# draft6.net
KiCad netlist of a schematic drawn in EAGLE
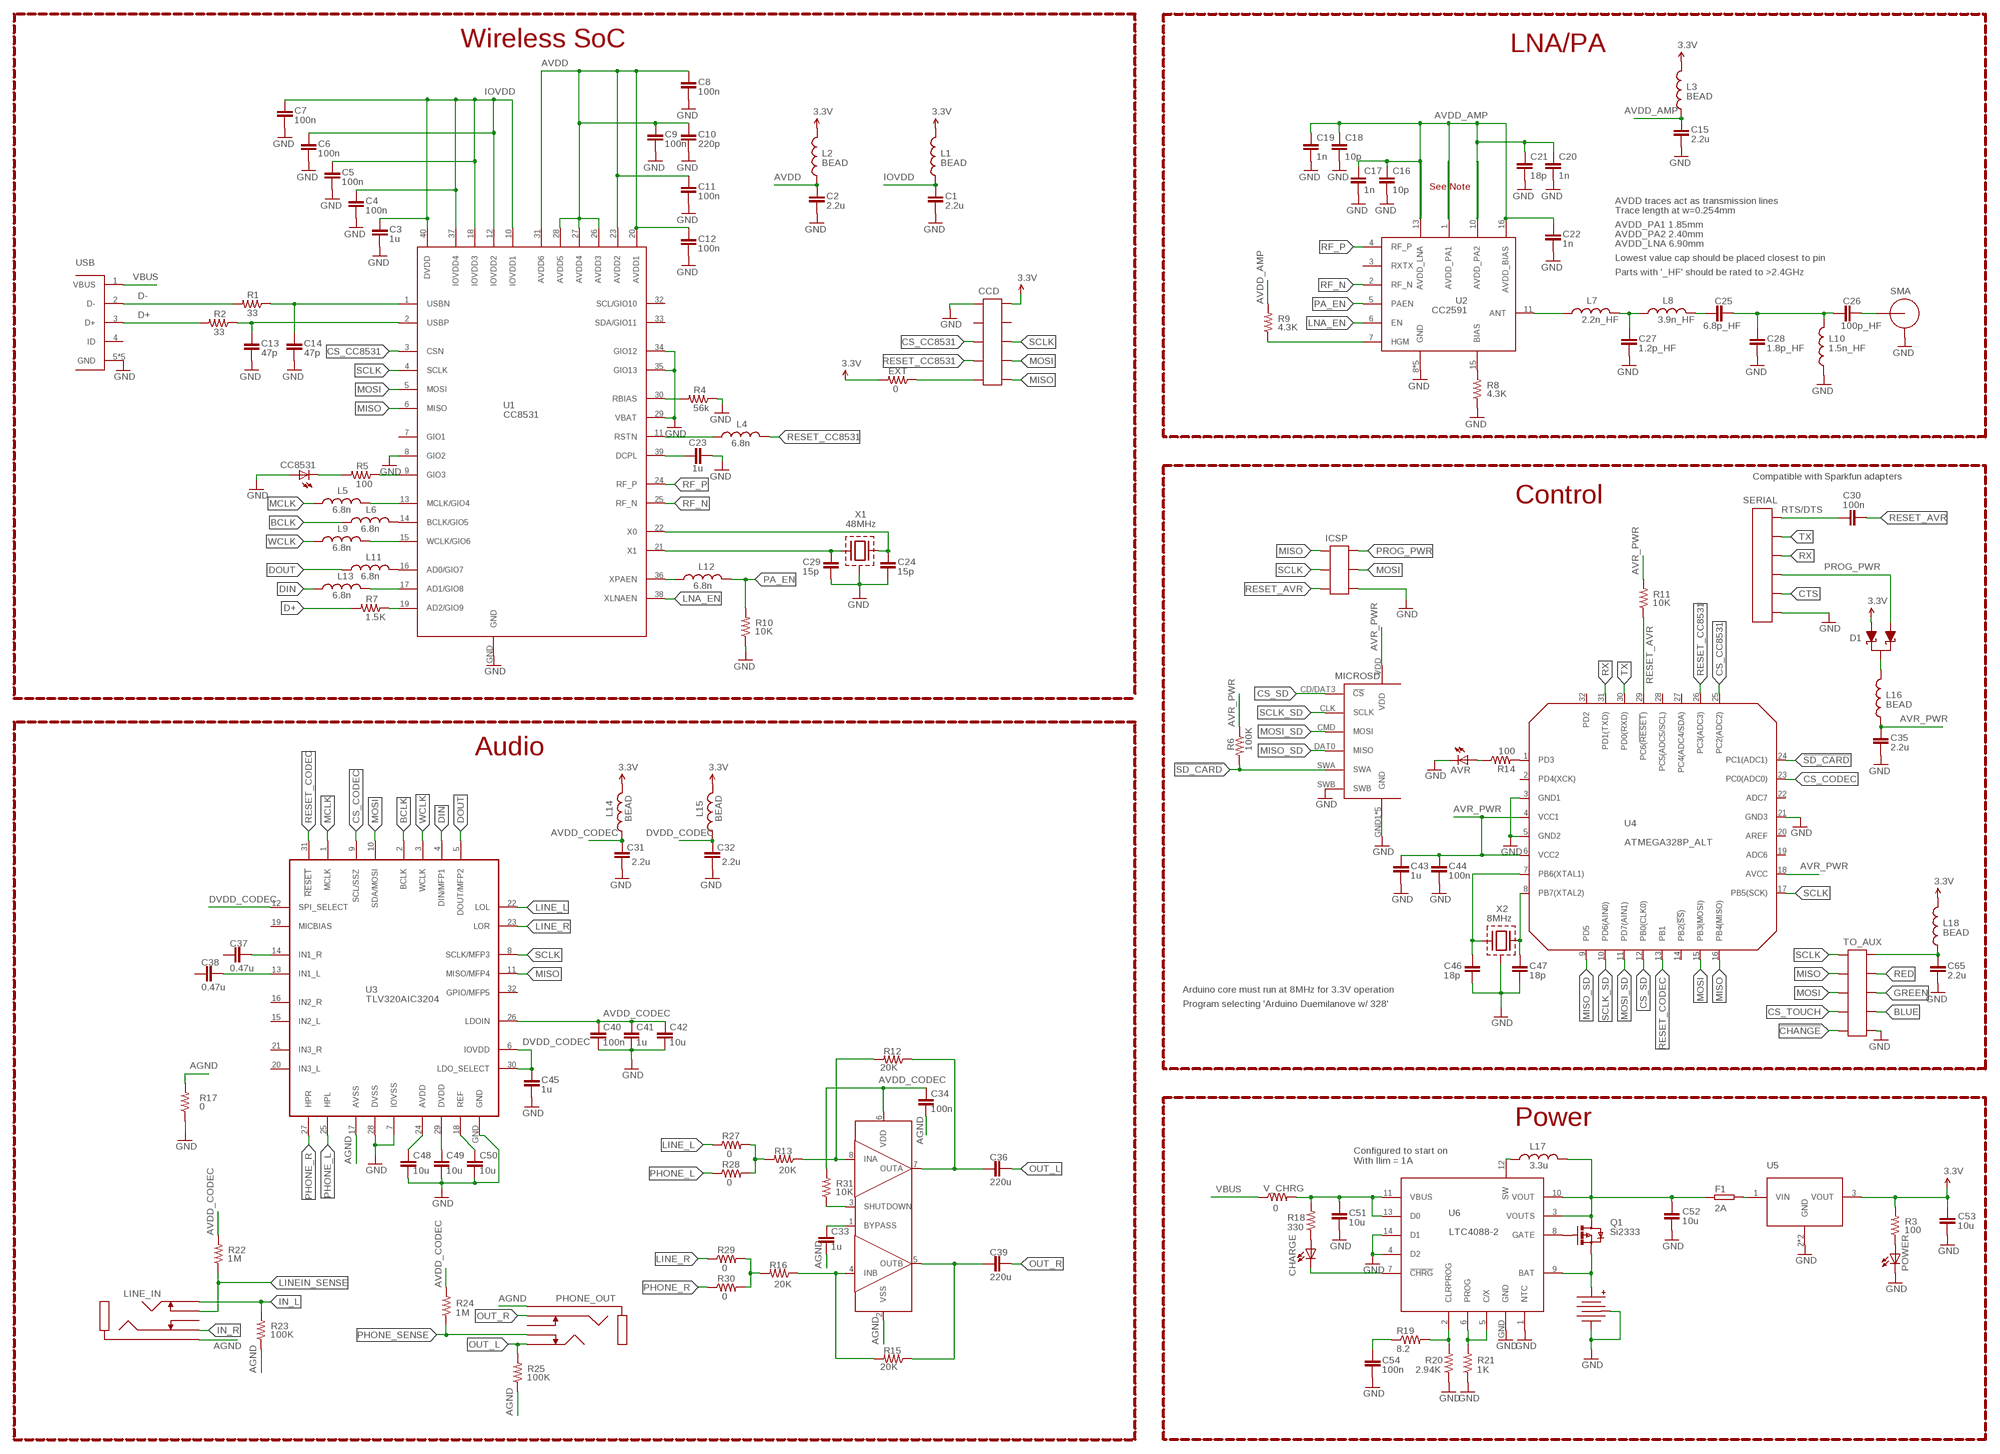
[diagram p0: schematic, sheet 1, part 1 of 2]
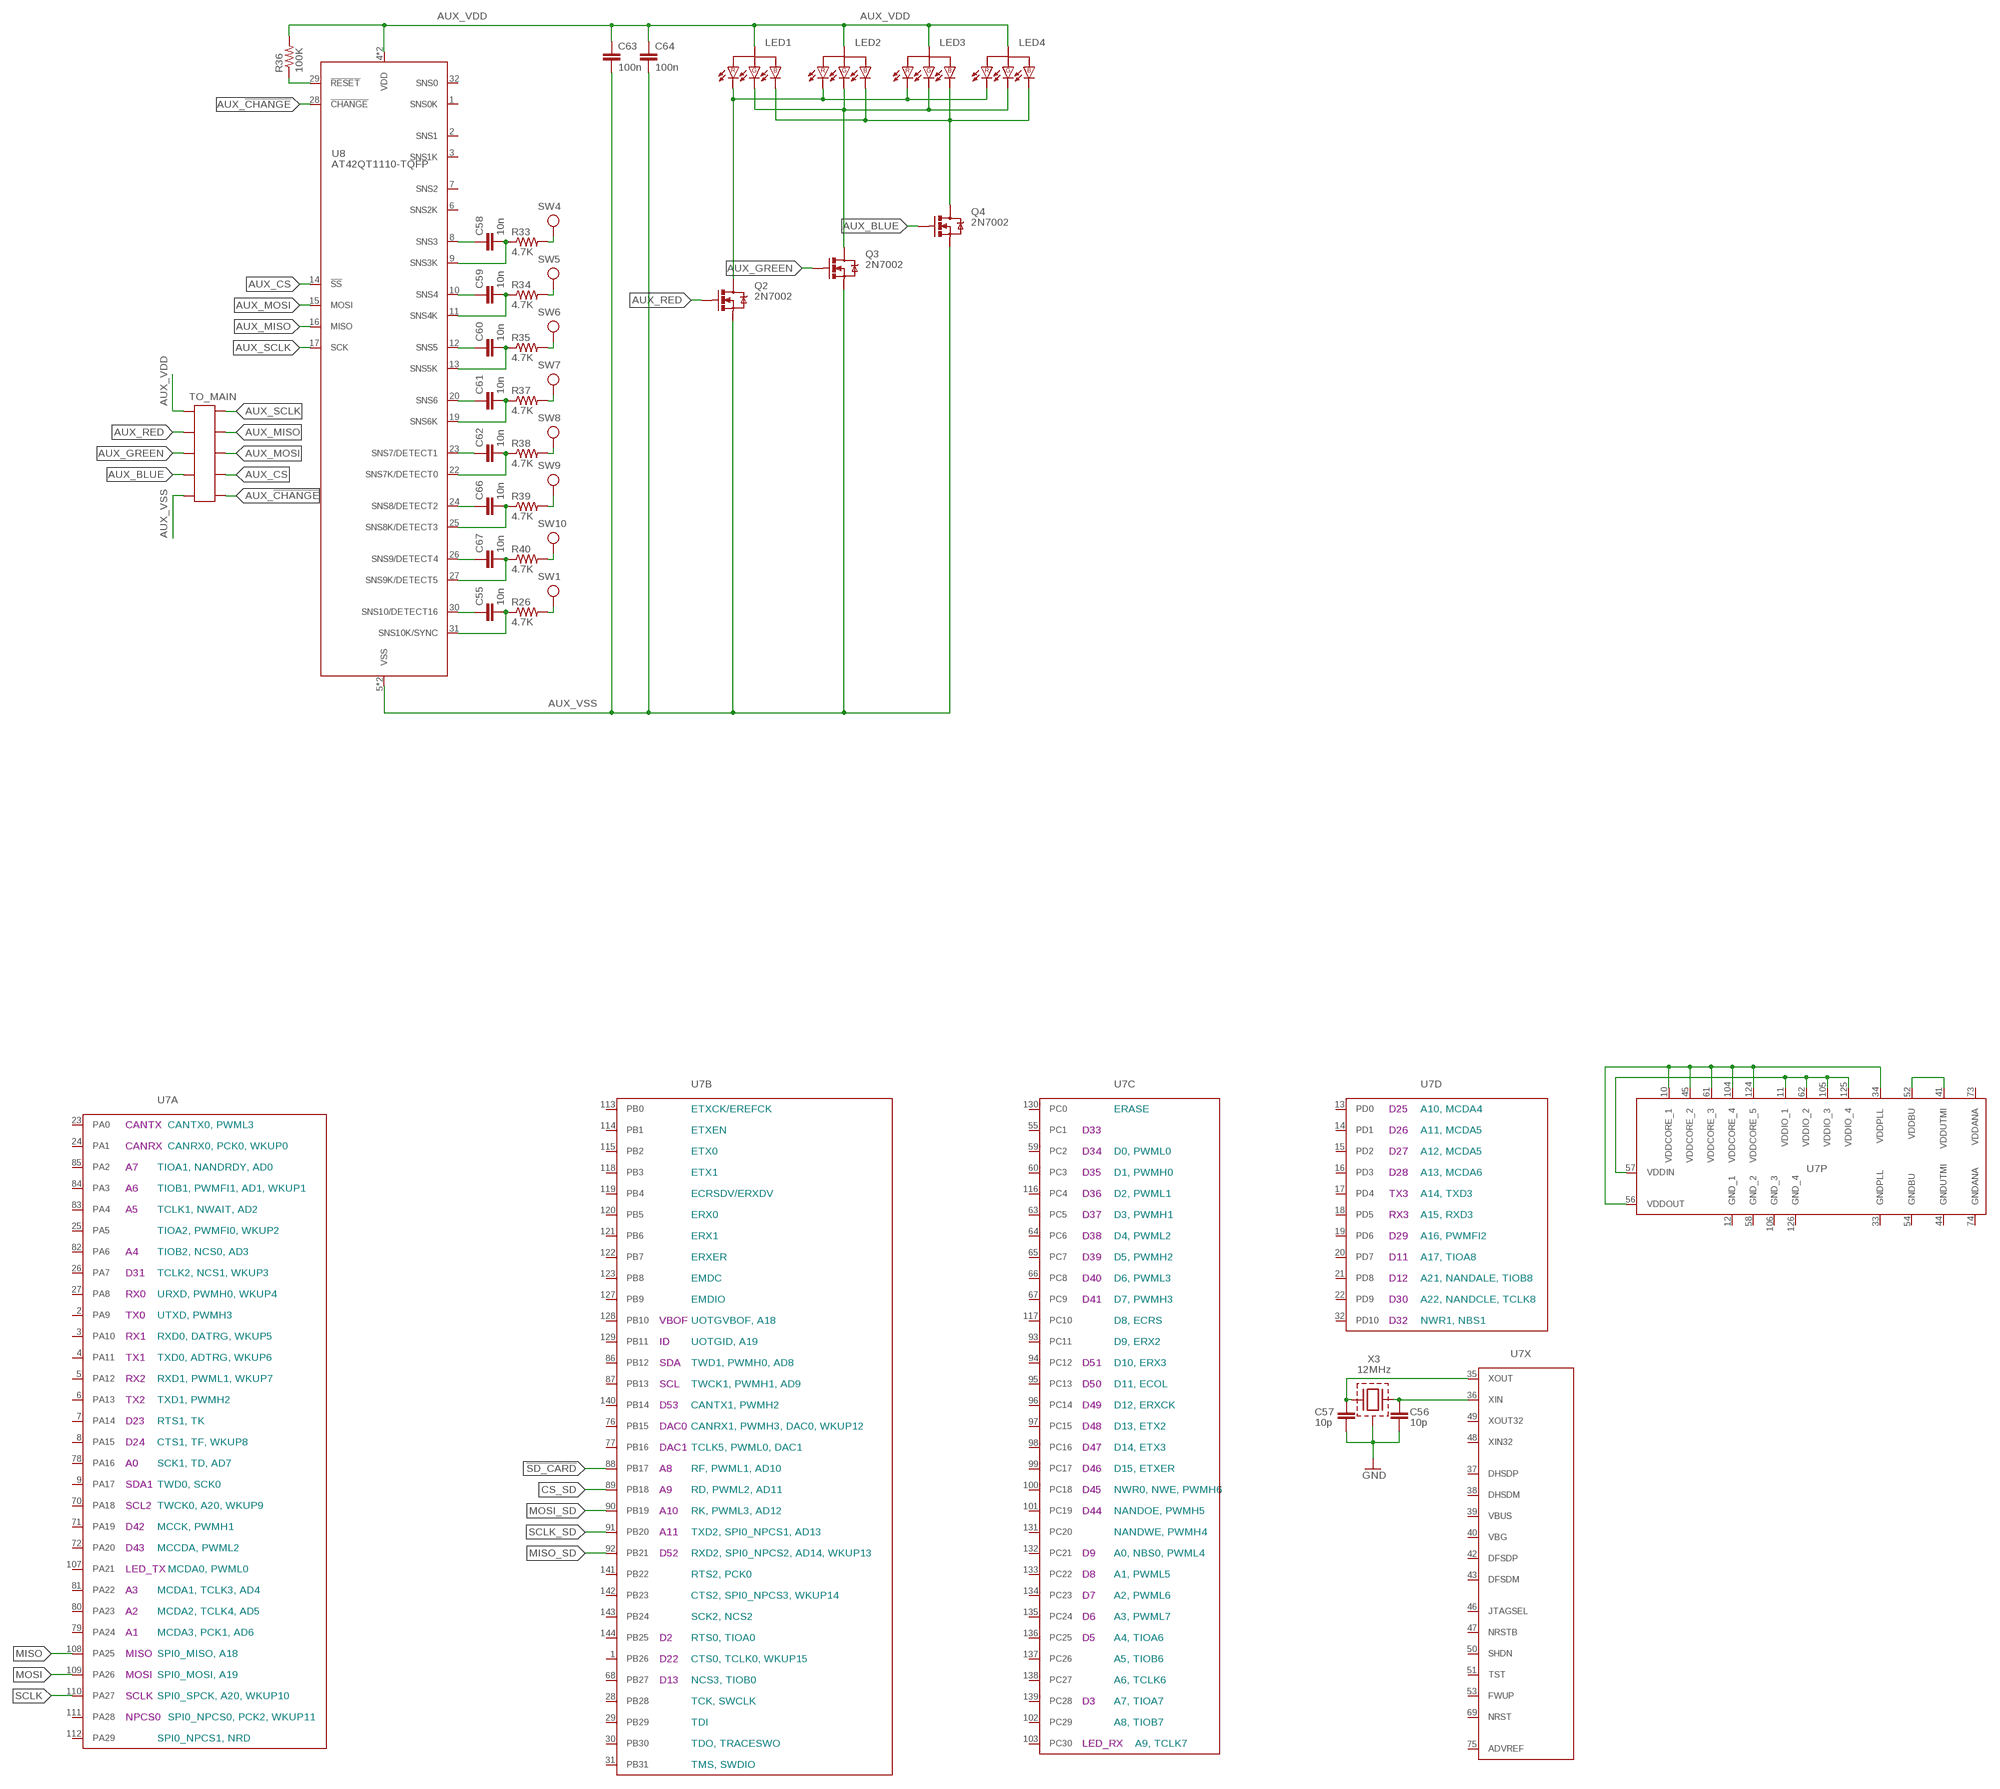
[diagram p1: schematic, sheet 1, part 2 of 2]

(export (version "E")
  (design (tool "Eeschema 10.0.6"))
  (components
    (comp (ref "AVR")
      (value "LED1206")
      (footprint "eagle-import:LED-1206")
      (libsource (lib "eagle-import") (part "LED1206"))
    )
    (comp (ref "B1")
      (value "BATTERY-LIPO-JST")
      (footprint "eagle-import:1775469-2")
      (libsource (lib "eagle-import") (part "BATTERY-LIPO-JST"))
    )
    (comp (ref "C1")
      (value "2.2u")
      (footprint "eagle-import:C0603")
      (libsource (lib "eagle-import") (part "rcl_C-EUC0603"))
    )
    (comp (ref "C2")
      (value "2.2u")
      (footprint "eagle-import:C0603")
      (libsource (lib "eagle-import") (part "rcl_C-EUC0603"))
    )
    (comp (ref "C3")
      (value "1u")
      (footprint "eagle-import:C0603")
      (libsource (lib "eagle-import") (part "rcl_C-EUC0603"))
    )
    (comp (ref "C4")
      (value "100n")
      (footprint "eagle-import:C0603")
      (libsource (lib "eagle-import") (part "rcl_C-EUC0603"))
    )
    (comp (ref "C5")
      (value "100n")
      (footprint "eagle-import:C0603")
      (libsource (lib "eagle-import") (part "rcl_C-EUC0603"))
    )
    (comp (ref "C6")
      (value "100n")
      (footprint "eagle-import:C0603")
      (libsource (lib "eagle-import") (part "rcl_C-EUC0603"))
    )
    (comp (ref "C7")
      (value "100n")
      (footprint "eagle-import:C0603")
      (libsource (lib "eagle-import") (part "rcl_C-EUC0603"))
    )
    (comp (ref "C8")
      (value "100n")
      (footprint "eagle-import:C0603")
      (libsource (lib "eagle-import") (part "rcl_C-EUC0603"))
    )
    (comp (ref "C9")
      (value "100n")
      (footprint "eagle-import:C0603")
      (libsource (lib "eagle-import") (part "rcl_C-EUC0603"))
    )
    (comp (ref "C10")
      (value "220p")
      (footprint "eagle-import:C0603")
      (libsource (lib "eagle-import") (part "rcl_C-EUC0603"))
    )
    (comp (ref "C11")
      (value "100n")
      (footprint "eagle-import:C0603")
      (libsource (lib "eagle-import") (part "rcl_C-EUC0603"))
    )
    (comp (ref "C12")
      (value "100n")
      (footprint "eagle-import:C0603")
      (libsource (lib "eagle-import") (part "rcl_C-EUC0603"))
    )
    (comp (ref "C13")
      (value "47p")
      (footprint "eagle-import:C0603")
      (libsource (lib "eagle-import") (part "rcl_C-EUC0603"))
    )
    (comp (ref "C14")
      (value "47p")
      (footprint "eagle-import:C0603")
      (libsource (lib "eagle-import") (part "rcl_C-EUC0603"))
    )
    (comp (ref "C15")
      (value "2.2u")
      (footprint "eagle-import:C0603")
      (libsource (lib "eagle-import") (part "rcl_C-EUC0603"))
    )
    (comp (ref "C16")
      (value "10p")
      (footprint "eagle-import:C0603")
      (libsource (lib "eagle-import") (part "rcl_C-EUC0603"))
    )
    (comp (ref "C17")
      (value "1n")
      (footprint "eagle-import:C0603")
      (libsource (lib "eagle-import") (part "rcl_C-EUC0603"))
    )
    (comp (ref "C18")
      (value "10p")
      (footprint "eagle-import:C0603")
      (libsource (lib "eagle-import") (part "rcl_C-EUC0603"))
    )
    (comp (ref "C19")
      (value "1n")
      (footprint "eagle-import:C0603")
      (libsource (lib "eagle-import") (part "rcl_C-EUC0603"))
    )
    (comp (ref "C20")
      (value "1n")
      (footprint "eagle-import:C0603")
      (libsource (lib "eagle-import") (part "rcl_C-EUC0603"))
    )
    (comp (ref "C21")
      (value "18p")
      (footprint "eagle-import:C0603")
      (libsource (lib "eagle-import") (part "rcl_C-EUC0603"))
    )
    (comp (ref "C22")
      (value "1n")
      (footprint "eagle-import:C0603")
      (libsource (lib "eagle-import") (part "rcl_C-EUC0603"))
    )
    (comp (ref "C23")
      (value "1u")
      (footprint "eagle-import:C0603")
      (libsource (lib "eagle-import") (part "rcl_C-EUC0603"))
    )
    (comp (ref "C24")
      (value "15p")
      (footprint "eagle-import:C0603")
      (libsource (lib "eagle-import") (part "rcl_C-EUC0603"))
    )
    (comp (ref "C25")
      (value "6.8p_HF")
      (footprint "eagle-import:C0603")
      (libsource (lib "eagle-import") (part "rcl_C-EUC0603"))
    )
    (comp (ref "C26")
      (value "100p_HF")
      (footprint "eagle-import:C0603")
      (libsource (lib "eagle-import") (part "rcl_C-EUC0603"))
    )
    (comp (ref "C27")
      (value "1.2p_HF")
      (footprint "eagle-import:C0603")
      (libsource (lib "eagle-import") (part "rcl_C-EUC0603"))
    )
    (comp (ref "C28")
      (value "1.8p_HF")
      (footprint "eagle-import:C0603")
      (libsource (lib "eagle-import") (part "rcl_C-EUC0603"))
    )
    (comp (ref "C29")
      (value "15p")
      (footprint "eagle-import:C0603")
      (libsource (lib "eagle-import") (part "rcl_C-EUC0603"))
    )
    (comp (ref "C30")
      (value "100n")
      (footprint "eagle-import:C0603")
      (libsource (lib "eagle-import") (part "rcl_C-EUC0603"))
    )
    (comp (ref "C31")
      (value "2.2u")
      (footprint "eagle-import:C0603")
      (libsource (lib "eagle-import") (part "rcl_C-EUC0603"))
    )
    (comp (ref "C32")
      (value "2.2u")
      (footprint "eagle-import:C0603")
      (libsource (lib "eagle-import") (part "rcl_C-EUC0603"))
    )
    (comp (ref "C33")
      (value "1u")
      (footprint "eagle-import:C0603")
      (libsource (lib "eagle-import") (part "rcl_C-EUC0603"))
    )
    (comp (ref "C34")
      (value "100n")
      (footprint "eagle-import:C0603")
      (libsource (lib "eagle-import") (part "rcl_C-EUC0603"))
    )
    (comp (ref "C35")
      (value "2.2u")
      (footprint "eagle-import:C0603")
      (libsource (lib "eagle-import") (part "rcl_C-EUC0603"))
    )
    (comp (ref "C36")
      (value "220u")
      (footprint "eagle-import:C1210")
      (libsource (lib "eagle-import") (part "C-EUC1210"))
    )
    (comp (ref "C37")
      (value "0.47u")
      (footprint "eagle-import:C0603")
      (libsource (lib "eagle-import") (part "rcl_C-EUC0603"))
    )
    (comp (ref "C38")
      (value "0.47u")
      (footprint "eagle-import:C0603")
      (libsource (lib "eagle-import") (part "rcl_C-EUC0603"))
    )
    (comp (ref "C39")
      (value "220u")
      (footprint "eagle-import:C1210")
      (libsource (lib "eagle-import") (part "C-EUC1210"))
    )
    (comp (ref "C40")
      (value "100n")
      (footprint "eagle-import:C0603")
      (libsource (lib "eagle-import") (part "rcl_C-EUC0603"))
    )
    (comp (ref "C41")
      (value "1u")
      (footprint "eagle-import:C0603")
      (libsource (lib "eagle-import") (part "rcl_C-EUC0603"))
    )
    (comp (ref "C42")
      (value "10u")
      (footprint "eagle-import:C0603")
      (libsource (lib "eagle-import") (part "rcl_C-EUC0603"))
    )
    (comp (ref "C43")
      (value "1u")
      (footprint "eagle-import:C0603")
      (libsource (lib "eagle-import") (part "rcl_C-EUC0603"))
    )
    (comp (ref "C44")
      (value "100n")
      (footprint "eagle-import:C0603")
      (libsource (lib "eagle-import") (part "rcl_C-EUC0603"))
    )
    (comp (ref "C45")
      (value "1u")
      (footprint "eagle-import:C0603")
      (libsource (lib "eagle-import") (part "rcl_C-EUC0603"))
    )
    (comp (ref "C46")
      (value "18p")
      (footprint "eagle-import:C0603")
      (libsource (lib "eagle-import") (part "C-EUC0603"))
    )
    (comp (ref "C47")
      (value "18p")
      (footprint "eagle-import:C0603")
      (libsource (lib "eagle-import") (part "C-EUC0603"))
    )
    (comp (ref "C48")
      (value "10u")
      (footprint "eagle-import:C0603")
      (libsource (lib "eagle-import") (part "rcl_C-EUC0603"))
    )
    (comp (ref "C49")
      (value "10u")
      (footprint "eagle-import:C0603")
      (libsource (lib "eagle-import") (part "rcl_C-EUC0603"))
    )
    (comp (ref "C50")
      (value "10u")
      (footprint "eagle-import:C0603")
      (libsource (lib "eagle-import") (part "rcl_C-EUC0603"))
    )
    (comp (ref "C51")
      (value "10u")
      (footprint "eagle-import:C0603")
      (libsource (lib "eagle-import") (part "C-EUC0603"))
    )
    (comp (ref "C52")
      (value "10u")
      (footprint "eagle-import:C0603")
      (libsource (lib "eagle-import") (part "rcl_C-EUC0603"))
    )
    (comp (ref "C53")
      (value "10u")
      (footprint "eagle-import:C0603")
      (libsource (lib "eagle-import") (part "rcl_C-EUC0603"))
    )
    (comp (ref "C54")
      (value "100n")
      (footprint "eagle-import:C0603")
      (libsource (lib "eagle-import") (part "C-EUC0603"))
    )
    (comp (ref "C55")
      (value "10n")
      (footprint "eagle-import:C0603")
      (libsource (lib "eagle-import") (part "rcl_C-EUC0603"))
    )
    (comp (ref "C56")
      (value "10p")
      (footprint "eagle-import:C0603")
      (libsource (lib "eagle-import") (part "C-EUC0603"))
    )
    (comp (ref "C57")
      (value "10p")
      (footprint "eagle-import:C0603")
      (libsource (lib "eagle-import") (part "C-EUC0603"))
    )
    (comp (ref "C58")
      (value "10n")
      (footprint "eagle-import:C0603")
      (libsource (lib "eagle-import") (part "rcl_C-EUC0603"))
    )
    (comp (ref "C59")
      (value "10n")
      (footprint "eagle-import:C0603")
      (libsource (lib "eagle-import") (part "rcl_C-EUC0603"))
    )
    (comp (ref "C60")
      (value "10n")
      (footprint "eagle-import:C0603")
      (libsource (lib "eagle-import") (part "rcl_C-EUC0603"))
    )
    (comp (ref "C61")
      (value "10n")
      (footprint "eagle-import:C0603")
      (libsource (lib "eagle-import") (part "rcl_C-EUC0603"))
    )
    (comp (ref "C62")
      (value "10n")
      (footprint "eagle-import:C0603")
      (libsource (lib "eagle-import") (part "rcl_C-EUC0603"))
    )
    (comp (ref "C63")
      (value "100n")
      (footprint "eagle-import:C0603")
      (libsource (lib "eagle-import") (part "rcl_C-EUC0603"))
    )
    (comp (ref "C64")
      (value "100n")
      (footprint "eagle-import:C0603")
      (libsource (lib "eagle-import") (part "rcl_C-EUC0603"))
    )
    (comp (ref "C65")
      (value "2.2u")
      (footprint "eagle-import:C0603")
      (libsource (lib "eagle-import") (part "rcl_C-EUC0603"))
    )
    (comp (ref "C66")
      (value "10n")
      (footprint "eagle-import:C0603")
      (libsource (lib "eagle-import") (part "rcl_C-EUC0603"))
    )
    (comp (ref "C67")
      (value "10n")
      (footprint "eagle-import:C0603")
      (libsource (lib "eagle-import") (part "rcl_C-EUC0603"))
    )
    (comp (ref "CC8531")
      (value "LED1206")
      (footprint "eagle-import:LED-1206")
      (libsource (lib "eagle-import") (part "LED1206"))
    )
    (comp (ref "CCD")
      (value "HEADER-10P-SMD-MALE2")
      (footprint "eagle-import:HEADER-10P-1.27MM")
      (libsource (lib "eagle-import") (part "HEADER-10P-SMD-MALE2"))
    )
    (comp (ref "CHARGE")
      (value "LED1206")
      (footprint "eagle-import:LED-1206")
      (libsource (lib "eagle-import") (part "LED1206"))
    )
    (comp (ref "D1")
      (value "DUAL_SCHOTTKY")
      (footprint "eagle-import:SOT-23")
      (libsource (lib "eagle-import") (part "DUAL_SCHOTTKY"))
    )
    (comp (ref "EXT")
      (value "0")
      (footprint "eagle-import:R0603")
      (libsource (lib "eagle-import") (part "rcl_R-US_R0603"))
    )
    (comp (ref "F1")
      (value "2A")
      (footprint "eagle-import:1210")
      (libsource (lib "eagle-import") (part "PTC_FUSE"))
    )
    (comp (ref "ICSP")
      (value "HEADER-6P-SMD-1.27MM")
      (footprint "eagle-import:HEADER-6P-1.27MM")
      (libsource (lib "eagle-import") (part "HEADER-6P-SMD-1.27MM"))
    )
    (comp (ref "L1")
      (value "BEAD")
      (footprint "eagle-import:0603")
      (libsource (lib "eagle-import") (part "INDUCTOR0603"))
    )
    (comp (ref "L2")
      (value "BEAD")
      (footprint "eagle-import:0603")
      (libsource (lib "eagle-import") (part "INDUCTOR0603"))
    )
    (comp (ref "L3")
      (value "BEAD")
      (footprint "eagle-import:0603")
      (libsource (lib "eagle-import") (part "INDUCTOR0603"))
    )
    (comp (ref "L4")
      (value "6.8n")
      (footprint "eagle-import:0603")
      (libsource (lib "eagle-import") (part "INDUCTOR0603"))
    )
    (comp (ref "L5")
      (value "6.8n")
      (footprint "eagle-import:0603")
      (libsource (lib "eagle-import") (part "INDUCTOR0603"))
    )
    (comp (ref "L6")
      (value "6.8n")
      (footprint "eagle-import:0603")
      (libsource (lib "eagle-import") (part "INDUCTOR0603"))
    )
    (comp (ref "L7")
      (value "2.2n_HF")
      (footprint "eagle-import:0603")
      (libsource (lib "eagle-import") (part "INDUCTOR0603"))
    )
    (comp (ref "L8")
      (value "3.9n_HF")
      (footprint "eagle-import:0603")
      (libsource (lib "eagle-import") (part "INDUCTOR0603"))
    )
    (comp (ref "L9")
      (value "6.8n")
      (footprint "eagle-import:0603")
      (libsource (lib "eagle-import") (part "INDUCTOR0603"))
    )
    (comp (ref "L10")
      (value "1.5n_HF")
      (footprint "eagle-import:0603")
      (libsource (lib "eagle-import") (part "INDUCTOR0603"))
    )
    (comp (ref "L11")
      (value "6.8n")
      (footprint "eagle-import:0603")
      (libsource (lib "eagle-import") (part "INDUCTOR0603"))
    )
    (comp (ref "L12")
      (value "6.8n")
      (footprint "eagle-import:0603")
      (libsource (lib "eagle-import") (part "INDUCTOR0603"))
    )
    (comp (ref "L13")
      (value "6.8n")
      (footprint "eagle-import:0603")
      (libsource (lib "eagle-import") (part "INDUCTOR0603"))
    )
    (comp (ref "L14")
      (value "BEAD")
      (footprint "eagle-import:0603")
      (libsource (lib "eagle-import") (part "INDUCTOR0603"))
    )
    (comp (ref "L15")
      (value "BEAD")
      (footprint "eagle-import:0603")
      (libsource (lib "eagle-import") (part "INDUCTOR0603"))
    )
    (comp (ref "L16")
      (value "BEAD")
      (footprint "eagle-import:0603")
      (libsource (lib "eagle-import") (part "INDUCTOR0603"))
    )
    (comp (ref "L17")
      (value "3.3u")
      (footprint "eagle-import:IFSC-1111AB-01")
      (libsource (lib "eagle-import") (part "IFSC-1111AB-01"))
    )
    (comp (ref "L18")
      (value "BEAD")
      (footprint "eagle-import:0603")
      (libsource (lib "eagle-import") (part "INDUCTOR0603"))
    )
    (comp (ref "LED1")
      (value "LED_RGB")
      (footprint "eagle-import:PLCC-4")
      (libsource (lib "eagle-import") (part "LED_RGB"))
    )
    (comp (ref "LED2")
      (value "LED_RGB")
      (footprint "eagle-import:PLCC-4")
      (libsource (lib "eagle-import") (part "LED_RGB"))
    )
    (comp (ref "LED3")
      (value "LED_RGB")
      (footprint "eagle-import:PLCC-4")
      (libsource (lib "eagle-import") (part "LED_RGB"))
    )
    (comp (ref "LED4")
      (value "LED_RGB")
      (footprint "eagle-import:PLCC-4")
      (libsource (lib "eagle-import") (part "LED_RGB"))
    )
    (comp (ref "LINE_IN")
      (value "PHONE_SW-STX-35332-5N")
      (footprint "eagle-import:STX-35332-5N")
      (libsource (lib "eagle-import") (part "PHONE_SW-STX-35332-5N"))
    )
    (comp (ref "MICROSD")
      (value "MICROSD104031-0811")
      (footprint "eagle-import:MOLEX_104031-0811")
      (libsource (lib "eagle-import") (part "MICROSD104031-0811"))
    )
    (comp (ref "PHONE_OUT")
      (value "PHONE_SW-STX-35332-5N")
      (footprint "eagle-import:STX-35332-5N")
      (libsource (lib "eagle-import") (part "PHONE_SW-STX-35332-5N"))
    )
    (comp (ref "POWER")
      (value "LED1206")
      (footprint "eagle-import:LED-1206")
      (libsource (lib "eagle-import") (part "LED1206"))
    )
    (comp (ref "Q1")
      (value "Si2333")
      (footprint "eagle-import:SOT23-3")
      (libsource (lib "eagle-import") (part "MOSFET-PCHANNELSMD"))
    )
    (comp (ref "Q2")
      (value "2N7002")
      (footprint "eagle-import:SOT23-3")
      (libsource (lib "eagle-import") (part "MOSFET-NCHANNELSMD"))
    )
    (comp (ref "Q3")
      (value "2N7002")
      (footprint "eagle-import:SOT23-3")
      (libsource (lib "eagle-import") (part "MOSFET-NCHANNELSMD"))
    )
    (comp (ref "Q4")
      (value "2N7002")
      (footprint "eagle-import:SOT23-3")
      (libsource (lib "eagle-import") (part "MOSFET-NCHANNELSMD"))
    )
    (comp (ref "R1")
      (value "33")
      (footprint "eagle-import:R0603")
      (libsource (lib "eagle-import") (part "rcl_R-US_R0603"))
    )
    (comp (ref "R2")
      (value "33")
      (footprint "eagle-import:R0603")
      (libsource (lib "eagle-import") (part "rcl_R-US_R0603"))
    )
    (comp (ref "R3")
      (value "100")
      (footprint "eagle-import:R0603")
      (libsource (lib "eagle-import") (part "rcl_R-US_R0603"))
    )
    (comp (ref "R4")
      (value "56k")
      (footprint "eagle-import:R0603")
      (libsource (lib "eagle-import") (part "rcl_R-US_R0603"))
    )
    (comp (ref "R5")
      (value "100")
      (footprint "eagle-import:R0603")
      (libsource (lib "eagle-import") (part "rcl_R-US_R0603"))
    )
    (comp (ref "R6")
      (value "100K")
      (footprint "eagle-import:R0603")
      (libsource (lib "eagle-import") (part "rcl_R-US_R0603"))
    )
    (comp (ref "R7")
      (value "1.5K")
      (footprint "eagle-import:R0603")
      (libsource (lib "eagle-import") (part "rcl_R-US_R0603"))
    )
    (comp (ref "R8")
      (value "4.3K")
      (footprint "eagle-import:R0603")
      (libsource (lib "eagle-import") (part "rcl_R-US_R0603"))
    )
    (comp (ref "R9")
      (value "4.3K")
      (footprint "eagle-import:R0603")
      (libsource (lib "eagle-import") (part "rcl_R-US_R0603"))
    )
    (comp (ref "R10")
      (value "10K")
      (footprint "eagle-import:R0603")
      (libsource (lib "eagle-import") (part "rcl_R-US_R0603"))
    )
    (comp (ref "R11")
      (value "10K")
      (footprint "eagle-import:R0603")
      (libsource (lib "eagle-import") (part "rcl_R-US_R0603"))
    )
    (comp (ref "R12")
      (value "20K")
      (footprint "eagle-import:R0603")
      (libsource (lib "eagle-import") (part "R-US_R0603"))
    )
    (comp (ref "R13")
      (value "20K")
      (footprint "eagle-import:R0603")
      (libsource (lib "eagle-import") (part "R-US_R0603"))
    )
    (comp (ref "R14")
      (value "100")
      (footprint "eagle-import:R0603")
      (libsource (lib "eagle-import") (part "rcl_R-US_R0603"))
    )
    (comp (ref "R15")
      (value "20K")
      (footprint "eagle-import:R0603")
      (libsource (lib "eagle-import") (part "R-US_R0603"))
    )
    (comp (ref "R16")
      (value "20K")
      (footprint "eagle-import:R0603")
      (libsource (lib "eagle-import") (part "R-US_R0603"))
    )
    (comp (ref "R17")
      (value "0")
      (footprint "eagle-import:R0603")
      (libsource (lib "eagle-import") (part "rcl_R-US_R0603"))
    )
    (comp (ref "R18")
      (value "330")
      (footprint "eagle-import:R0603")
      (libsource (lib "eagle-import") (part "R-US_R0603"))
    )
    (comp (ref "R19")
      (value "8.2")
      (footprint "eagle-import:R0603")
      (libsource (lib "eagle-import") (part "R-US_R0603"))
    )
    (comp (ref "R20")
      (value "2.94K")
      (footprint "eagle-import:R0603")
      (libsource (lib "eagle-import") (part "R-US_R0603"))
    )
    (comp (ref "R21")
      (value "1K")
      (footprint "eagle-import:R0603")
      (libsource (lib "eagle-import") (part "R-US_R0603"))
    )
    (comp (ref "R22")
      (value "1M")
      (footprint "eagle-import:R0603")
      (libsource (lib "eagle-import") (part "rcl_R-US_R0603"))
    )
    (comp (ref "R23")
      (value "100K")
      (footprint "eagle-import:R0603")
      (libsource (lib "eagle-import") (part "rcl_R-US_R0603"))
    )
    (comp (ref "R24")
      (value "1M")
      (footprint "eagle-import:R0603")
      (libsource (lib "eagle-import") (part "rcl_R-US_R0603"))
    )
    (comp (ref "R25")
      (value "100K")
      (footprint "eagle-import:R0603")
      (libsource (lib "eagle-import") (part "rcl_R-US_R0603"))
    )
    (comp (ref "R26")
      (value "4.7K")
      (footprint "eagle-import:R0603")
      (libsource (lib "eagle-import") (part "rcl_R-US_R0603"))
    )
    (comp (ref "R27")
      (value "0")
      (footprint "eagle-import:R0603")
      (libsource (lib "eagle-import") (part "R-US_R0603"))
    )
    (comp (ref "R28")
      (value "0")
      (footprint "eagle-import:R0603")
      (libsource (lib "eagle-import") (part "R-US_R0603"))
    )
    (comp (ref "R29")
      (value "0")
      (footprint "eagle-import:R0603")
      (libsource (lib "eagle-import") (part "R-US_R0603"))
    )
    (comp (ref "R30")
      (value "0")
      (footprint "eagle-import:R0603")
      (libsource (lib "eagle-import") (part "R-US_R0603"))
    )
    (comp (ref "R31")
      (value "10K")
      (footprint "eagle-import:R0603")
      (libsource (lib "eagle-import") (part "rcl_R-US_R0603"))
    )
    (comp (ref "R33")
      (value "4.7K")
      (footprint "eagle-import:R0603")
      (libsource (lib "eagle-import") (part "rcl_R-US_R0603"))
    )
    (comp (ref "R34")
      (value "4.7K")
      (footprint "eagle-import:R0603")
      (libsource (lib "eagle-import") (part "rcl_R-US_R0603"))
    )
    (comp (ref "R35")
      (value "4.7K")
      (footprint "eagle-import:R0603")
      (libsource (lib "eagle-import") (part "rcl_R-US_R0603"))
    )
    (comp (ref "R36")
      (value "100K")
      (footprint "eagle-import:R0603")
      (libsource (lib "eagle-import") (part "rcl_R-US_R0603"))
    )
    (comp (ref "R37")
      (value "4.7K")
      (footprint "eagle-import:R0603")
      (libsource (lib "eagle-import") (part "rcl_R-US_R0603"))
    )
    (comp (ref "R38")
      (value "4.7K")
      (footprint "eagle-import:R0603")
      (libsource (lib "eagle-import") (part "rcl_R-US_R0603"))
    )
    (comp (ref "R39")
      (value "4.7K")
      (footprint "eagle-import:R0603")
      (libsource (lib "eagle-import") (part "rcl_R-US_R0603"))
    )
    (comp (ref "R40")
      (value "4.7K")
      (footprint "eagle-import:R0603")
      (libsource (lib "eagle-import") (part "rcl_R-US_R0603"))
    )
    (comp (ref "SERIAL")
      (value "HEADER-6X1-961106-5500")
      (footprint "eagle-import:HEADER-3M-961-6P-2.54MM")
      (libsource (lib "eagle-import") (part "HEADER-6X1-961106-5500"))
    )
    (comp (ref "SMA")
      (value "SMA-REVSMA-0.62")
      (footprint "eagle-import:CONREVSMA003.062")
      (libsource (lib "eagle-import") (part "SMA-REVSMA-0.62"))
    )
    (comp (ref "SW1")
      (value "TOUCH_PAD-CIRCLE-15MM")
      (footprint "eagle-import:TOUCH-CIRCLE-15MM")
      (libsource (lib "eagle-import") (part "TOUCH_PAD-CIRCLE-15MM"))
    )
    (comp (ref "SW4")
      (value "TOUCH_PAD-CIRCLE-15MM")
      (footprint "eagle-import:TOUCH-CIRCLE-15MM")
      (libsource (lib "eagle-import") (part "TOUCH_PAD-CIRCLE-15MM"))
    )
    (comp (ref "SW5")
      (value "TOUCH_PAD-CIRCLE-15MM")
      (footprint "eagle-import:TOUCH-CIRCLE-15MM")
      (libsource (lib "eagle-import") (part "TOUCH_PAD-CIRCLE-15MM"))
    )
    (comp (ref "SW6")
      (value "TOUCH_PAD-CIRCLE-15MM")
      (footprint "eagle-import:TOUCH-CIRCLE-15MM")
      (libsource (lib "eagle-import") (part "TOUCH_PAD-CIRCLE-15MM"))
    )
    (comp (ref "SW7")
      (value "TOUCH_PAD-CIRCLE-15MM")
      (footprint "eagle-import:TOUCH-CIRCLE-15MM")
      (libsource (lib "eagle-import") (part "TOUCH_PAD-CIRCLE-15MM"))
    )
    (comp (ref "SW8")
      (value "TOUCH_PAD-CIRCLE-15MM")
      (footprint "eagle-import:TOUCH-CIRCLE-15MM")
      (libsource (lib "eagle-import") (part "TOUCH_PAD-CIRCLE-15MM"))
    )
    (comp (ref "SW9")
      (value "TOUCH_PAD-CIRCLE-15MM")
      (footprint "eagle-import:TOUCH-CIRCLE-15MM")
      (libsource (lib "eagle-import") (part "TOUCH_PAD-CIRCLE-15MM"))
    )
    (comp (ref "SW10")
      (value "TOUCH_PAD-CIRCLE-15MM")
      (footprint "eagle-import:TOUCH-CIRCLE-15MM")
      (libsource (lib "eagle-import") (part "TOUCH_PAD-CIRCLE-15MM"))
    )
    (comp (ref "TO_AUX")
      (value "HEADER-10P-SMD-2MM-FEMALE")
      (footprint "eagle-import:M22-63405")
      (libsource (lib "eagle-import") (part "HEADER-10P-SMD-2MM-FEMALE"))
    )
    (comp (ref "TO_MAIN")
      (value "HEADER-10P-SMD-2MM-MALE")
      (footprint "eagle-import:M22-53205")
      (libsource (lib "eagle-import") (part "HEADER-10P-SMD-2MM-MALE"))
    )
    (comp (ref "U$15")
      (value "LM4881")
      (footprint "eagle-import:SO08")
      (libsource (lib "eagle-import") (part "LM4881"))
    )
    (comp (ref "U1")
      (value "CC8531")
      (footprint "eagle-import:S-PVQFN-N40")
      (libsource (lib "eagle-import") (part "CC8531"))
    )
    (comp (ref "U2")
      (value "CC2591")
      (footprint "eagle-import:S-PVQFN-N16")
      (libsource (lib "eagle-import") (part "CC2591"))
    )
    (comp (ref "U3")
      (value "TLV320AIC3204")
      (footprint "eagle-import:S-PVQFN-N32")
      (libsource (lib "eagle-import") (part "TLV320AIC3204"))
    )
    (comp (ref "U4")
      (value "ATMEGA328P_ALT")
      (footprint "eagle-import:S-PQFP-N32")
      (libsource (lib "eagle-import") (part "ATMEGA328P_ALT"))
    )
    (comp (ref "U5")
      (value "MCP1826-SOT223")
      (footprint "eagle-import:SOT-223")
      (libsource (lib "eagle-import") (part "MCP1826-SOT223"))
    )
    (comp (ref "U6")
      (value "LTC4088-2")
      (footprint "eagle-import:DFN-14")
      (libsource (lib "eagle-import") (part "LTC4088-1/2"))
    )
    (comp (ref "U7")
      (value "ATSAM3X8E_ALT-LQFP-144")
      (footprint "eagle-import:LQFP-144")
      (libsource (lib "eagle-import") (part "ATSAM3X8E_ALT-LQFP-144"))
    )
    (comp (ref "U8")
      (value "AT42QT1110-TQFP")
      (footprint "eagle-import:S-PQFP-N32")
      (libsource (lib "eagle-import") (part "AT42QT1110-TQFP"))
    )
    (comp (ref "USB")
      (value "USB_MICRO_AB")
      (footprint "eagle-import:USB_MICRO_AB")
      (libsource (lib "eagle-import") (part "USB_MICRO_AB"))
    )
    (comp (ref "V_CHRG")
      (value "0")
      (footprint "eagle-import:R0603")
      (libsource (lib "eagle-import") (part "R-US_R0603"))
    )
    (comp (ref "X1")
      (value "48MHz")
      (footprint "eagle-import:ABM3C")
      (libsource (lib "eagle-import") (part "XTAL-ABRACONABM3C"))
    )
    (comp (ref "X2")
      (value "8MHz")
      (footprint "eagle-import:ABM3B")
      (libsource (lib "eagle-import") (part "XTAL-ABRACONABM3B"))
    )
    (comp (ref "X3")
      (value "12MHz")
      (footprint "eagle-import:ABM8G")
      (libsource (lib "eagle-import") (part "XTAL-ABRACONABM8G"))
    )
  )
  (nets
    (net (code "1") (name "/AGND") (class "Default")
      (node (ref "C33") (pin "2") (pinfunction "2_2") (pintype "passive"))
      (node (ref "C34") (pin "2") (pinfunction "2_2") (pintype "passive"))
      (node (ref "LINE_IN") (pin "5") (pinfunction "GND_5") (pintype "bidirectional"))
      (node (ref "PHONE_OUT") (pin "5") (pinfunction "GND_5") (pintype "bidirectional"))
      (node (ref "R17") (pin "2") (pinfunction "2_2") (pintype "passive"))
      (node (ref "R23") (pin "1") (pinfunction "1_1") (pintype "passive"))
      (node (ref "R25") (pin "1") (pinfunction "1_1") (pintype "passive"))
      (node (ref "U$15") (pin "2") (pinfunction "VSS_2") (pintype "bidirectional"))
      (node (ref "U3") (pin "17") (pinfunction "AVSS_17") (pintype "bidirectional"))
    )
    (net (code "2") (name "/AUX_VDD") (class "Default")
      (node (ref "C63") (pin "1") (pinfunction "1_1") (pintype "passive"))
      (node (ref "C64") (pin "1") (pinfunction "1_1") (pintype "passive"))
      (node (ref "LED1") (pin "2") (pinfunction "A_2") (pintype "passive"))
      (node (ref "LED1") (pin "2-2") (pinfunction "A_2-2") (pintype "passive"))
      (node (ref "LED2") (pin "2") (pinfunction "A_2") (pintype "passive"))
      (node (ref "LED2") (pin "2-2") (pinfunction "A_2-2") (pintype "passive"))
      (node (ref "LED3") (pin "2") (pinfunction "A_2") (pintype "passive"))
      (node (ref "LED3") (pin "2-2") (pinfunction "A_2-2") (pintype "passive"))
      (node (ref "LED4") (pin "2") (pinfunction "A_2") (pintype "passive"))
      (node (ref "LED4") (pin "2-2") (pinfunction "A_2-2") (pintype "passive"))
      (node (ref "R36") (pin "2") (pinfunction "2_2") (pintype "passive"))
      (node (ref "TO_MAIN") (pin "1") (pinfunction "1_1") (pintype "bidirectional"))
      (node (ref "U8") (pin "18") (pinfunction "VDD_18") (pintype "bidirectional"))
      (node (ref "U8") (pin "4") (pinfunction "VDD_4") (pintype "bidirectional"))
    )
    (net (code "3") (name "/AUX_VSS") (class "Default")
      (node (ref "C63") (pin "2") (pinfunction "2_2") (pintype "passive"))
      (node (ref "C64") (pin "2") (pinfunction "2_2") (pintype "passive"))
      (node (ref "Q2") (pin "2") (pinfunction "S_2") (pintype "passive"))
      (node (ref "Q3") (pin "2") (pinfunction "S_2") (pintype "passive"))
      (node (ref "Q4") (pin "2") (pinfunction "S_2") (pintype "passive"))
      (node (ref "TO_MAIN") (pin "9") (pinfunction "9_9") (pintype "bidirectional"))
      (node (ref "U8") (pin "21") (pinfunction "VSS_21") (pintype "bidirectional"))
      (node (ref "U8") (pin "5") (pinfunction "VSS_5") (pintype "bidirectional"))
    )
    (net (code "4") (name "/AUX_~{CHANGE}") (class "Default")
      (node (ref "TO_MAIN") (pin "10") (pinfunction "10_10") (pintype "bidirectional"))
      (node (ref "U8") (pin "28") (pinfunction "~{CHANGE}_28") (pintype "bidirectional"))
    )
    (net (code "5") (name "/AVDD") (class "Default")
      (node (ref "C10") (pin "1") (pinfunction "1_1") (pintype "passive"))
      (node (ref "C11") (pin "1") (pinfunction "1_1") (pintype "passive"))
      (node (ref "C12") (pin "1") (pinfunction "1_1") (pintype "passive"))
      (node (ref "C2") (pin "1") (pinfunction "1_1") (pintype "passive"))
      (node (ref "C8") (pin "1") (pinfunction "1_1") (pintype "passive"))
      (node (ref "C9") (pin "1") (pinfunction "1_1") (pintype "passive"))
      (node (ref "L2") (pin "1") (pinfunction "1_1") (pintype "passive"))
      (node (ref "U1") (pin "20") (pinfunction "AVDD1_20") (pintype "bidirectional"))
      (node (ref "U1") (pin "23") (pinfunction "AVDD2_23") (pintype "bidirectional"))
      (node (ref "U1") (pin "26") (pinfunction "AVDD3_26") (pintype "bidirectional"))
      (node (ref "U1") (pin "27") (pinfunction "AVDD4_27") (pintype "bidirectional"))
      (node (ref "U1") (pin "28") (pinfunction "AVDD5_28") (pintype "bidirectional"))
      (node (ref "U1") (pin "31") (pinfunction "AVDD6_31") (pintype "bidirectional"))
    )
    (net (code "6") (name "/AVDD_AMP") (class "Default")
      (node (ref "C15") (pin "1") (pinfunction "1_1") (pintype "passive"))
      (node (ref "C16") (pin "1") (pinfunction "1_1") (pintype "passive"))
      (node (ref "C17") (pin "1") (pinfunction "1_1") (pintype "passive"))
      (node (ref "C18") (pin "1") (pinfunction "1_1") (pintype "passive"))
      (node (ref "C19") (pin "1") (pinfunction "1_1") (pintype "passive"))
      (node (ref "C20") (pin "1") (pinfunction "1_1") (pintype "passive"))
      (node (ref "C21") (pin "1") (pinfunction "1_1") (pintype "passive"))
      (node (ref "C22") (pin "1") (pinfunction "1_1") (pintype "passive"))
      (node (ref "L3") (pin "1") (pinfunction "1_1") (pintype "passive"))
      (node (ref "R9") (pin "2") (pinfunction "2_2") (pintype "passive"))
      (node (ref "U2") (pin "1") (pinfunction "AVDD_PA1_1") (pintype "bidirectional"))
      (node (ref "U2") (pin "10") (pinfunction "AVDD_PA2_10") (pintype "bidirectional"))
      (node (ref "U2") (pin "13") (pinfunction "AVDD_LNA_13") (pintype "bidirectional"))
      (node (ref "U2") (pin "16") (pinfunction "AVDD_BIAS_16") (pintype "bidirectional"))
    )
    (net (code "7") (name "/AVDD_CODEC") (class "Default")
      (node (ref "C31") (pin "1") (pinfunction "1_1") (pintype "passive"))
      (node (ref "C34") (pin "1") (pinfunction "1_1") (pintype "passive"))
      (node (ref "C40") (pin "1") (pinfunction "1_1") (pintype "passive"))
      (node (ref "C41") (pin "1") (pinfunction "1_1") (pintype "passive"))
      (node (ref "C42") (pin "1") (pinfunction "1_1") (pintype "passive"))
      (node (ref "L14") (pin "1") (pinfunction "1_1") (pintype "passive"))
      (node (ref "R22") (pin "2") (pinfunction "2_2") (pintype "passive"))
      (node (ref "R24") (pin "2") (pinfunction "2_2") (pintype "passive"))
      (node (ref "R31") (pin "2") (pinfunction "2_2") (pintype "passive"))
      (node (ref "U$15") (pin "6") (pinfunction "VDD_6") (pintype "bidirectional"))
      (node (ref "U3") (pin "26") (pinfunction "LDOIN_26") (pintype "bidirectional"))
    )
    (net (code "8") (name "/AVR_PWR") (class "Default")
      (node (ref "C35") (pin "1") (pinfunction "1_1") (pintype "passive"))
      (node (ref "C43") (pin "1") (pinfunction "1_1") (pintype "passive"))
      (node (ref "C44") (pin "1") (pinfunction "1_1") (pintype "passive"))
      (node (ref "L16") (pin "1") (pinfunction "1_1") (pintype "passive"))
      (node (ref "MICROSD") (pin "VDD") (pinfunction "VDD_VDD") (pintype "bidirectional"))
      (node (ref "R11") (pin "2") (pinfunction "2_2") (pintype "passive"))
      (node (ref "R6") (pin "1") (pinfunction "1_1") (pintype "passive"))
      (node (ref "U4") (pin "18") (pinfunction "AVCC_18") (pintype "bidirectional"))
      (node (ref "U4") (pin "4") (pinfunction "VCC1_4") (pintype "bidirectional"))
      (node (ref "U4") (pin "6") (pinfunction "VCC2_6") (pintype "bidirectional"))
    )
    (net (code "9") (name "/D-") (class "Default")
      (node (ref "R1") (pin "2") (pinfunction "2_2") (pintype "passive"))
      (node (ref "USB") (pin "2") (pinfunction "D-_2") (pintype "bidirectional"))
    )
    (net (code "10") (name "/DVDD_CODEC") (class "Default")
      (node (ref "C32") (pin "1") (pinfunction "1_1") (pintype "passive"))
      (node (ref "C45") (pin "1") (pinfunction "1_1") (pintype "passive"))
      (node (ref "L15") (pin "1") (pinfunction "1_1") (pintype "passive"))
      (node (ref "U3") (pin "12") (pinfunction "SPI_SELECT_12") (pintype "bidirectional"))
      (node (ref "U3") (pin "30") (pinfunction "LDO_SELECT_30") (pintype "bidirectional"))
      (node (ref "U3") (pin "6") (pinfunction "IOVDD_6") (pintype "bidirectional"))
    )
    (net (code "11") (name "/IOVDD") (class "Default")
      (node (ref "C1") (pin "1") (pinfunction "1_1") (pintype "passive"))
      (node (ref "C3") (pin "1") (pinfunction "1_1") (pintype "passive"))
      (node (ref "C4") (pin "1") (pinfunction "1_1") (pintype "passive"))
      (node (ref "C5") (pin "1") (pinfunction "1_1") (pintype "passive"))
      (node (ref "C6") (pin "1") (pinfunction "1_1") (pintype "passive"))
      (node (ref "C7") (pin "1") (pinfunction "1_1") (pintype "passive"))
      (node (ref "L1") (pin "1") (pinfunction "1_1") (pintype "passive"))
      (node (ref "U1") (pin "10") (pinfunction "IOVDD1_10") (pintype "bidirectional"))
      (node (ref "U1") (pin "12") (pinfunction "IOVDD2_12") (pintype "bidirectional"))
      (node (ref "U1") (pin "18") (pinfunction "IOVDD3_18") (pintype "bidirectional"))
      (node (ref "U1") (pin "37") (pinfunction "IOVDD4_37") (pintype "bidirectional"))
      (node (ref "U1") (pin "40") (pinfunction "DVDD_40") (pintype "bidirectional"))
    )
    (net (code "12") (name "/RTS{slash}DTS") (class "Default")
      (node (ref "C30") (pin "1") (pinfunction "1_1") (pintype "passive"))
      (node (ref "SERIAL") (pin "6") (pinfunction "6_6") (pintype "bidirectional"))
    )
    (net (code "13") (name "/VBUS") (class "Default")
      (node (ref "USB") (pin "1") (pinfunction "VBUS_1") (pintype "bidirectional"))
      (node (ref "V_CHRG") (pin "1") (pinfunction "1_1") (pintype "passive"))
    )
    (net (code "14") (name "/~{CHANGE}") (class "Default")
      (node (ref "TO_AUX") (pin "9") (pinfunction "9_9") (pintype "bidirectional"))
    )
    (net (code "15") (name "/~{SD_CARD}") (class "Default")
      (node (ref "MICROSD") (pin "SWA") (pinfunction "SWA_SWA") (pintype "bidirectional"))
      (node (ref "R6") (pin "2") (pinfunction "2_2") (pintype "passive"))
      (node (ref "U4") (pin "24") (pinfunction "PC1(ADC1)_24") (pintype "bidirectional"))
      (node (ref "U7") (pin "88") (pinfunction "PB17_88") (pintype "bidirectional"))
    )
    (net (code "16") (name "3.3V") (class "Default")
      (node (ref "C53") (pin "1") (pinfunction "1_1") (pintype "passive"))
      (node (ref "CCD") (pin "2") (pinfunction "2_2") (pintype "bidirectional"))
      (node (ref "D1") (pin "1") (pinfunction "A1_1") (pintype "passive"))
      (node (ref "EXT") (pin "2") (pinfunction "2_2") (pintype "passive"))
      (node (ref "L1") (pin "2") (pinfunction "2_2") (pintype "passive"))
      (node (ref "L14") (pin "2") (pinfunction "2_2") (pintype "passive"))
      (node (ref "L15") (pin "2") (pinfunction "2_2") (pintype "passive"))
      (node (ref "L18") (pin "2") (pinfunction "2_2") (pintype "passive"))
      (node (ref "L2") (pin "2") (pinfunction "2_2") (pintype "passive"))
      (node (ref "L3") (pin "2") (pinfunction "2_2") (pintype "passive"))
      (node (ref "R3") (pin "2") (pinfunction "2_2") (pintype "passive"))
      (node (ref "U5") (pin "3") (pinfunction "VOUT_3") (pintype "bidirectional"))
    )
    (net (code "17") (name "AUX_BLUE") (class "Default")
      (node (ref "Q4") (pin "1") (pinfunction "G_1") (pintype "passive"))
      (node (ref "TO_MAIN") (pin "7") (pinfunction "7_7") (pintype "bidirectional"))
    )
    (net (code "18") (name "AUX_CS") (class "Default")
      (node (ref "TO_MAIN") (pin "8") (pinfunction "8_8") (pintype "bidirectional"))
      (node (ref "U8") (pin "14") (pinfunction "~{SS}_14") (pintype "bidirectional"))
    )
    (net (code "19") (name "AUX_GREEN") (class "Default")
      (node (ref "Q3") (pin "1") (pinfunction "G_1") (pintype "passive"))
      (node (ref "TO_MAIN") (pin "5") (pinfunction "5_5") (pintype "bidirectional"))
    )
    (net (code "20") (name "AUX_MISO") (class "Default")
      (node (ref "TO_MAIN") (pin "4") (pinfunction "4_4") (pintype "bidirectional"))
      (node (ref "U8") (pin "16") (pinfunction "MISO_16") (pintype "bidirectional"))
    )
    (net (code "21") (name "AUX_MOSI") (class "Default")
      (node (ref "TO_MAIN") (pin "6") (pinfunction "6_6") (pintype "bidirectional"))
      (node (ref "U8") (pin "15") (pinfunction "MOSI_15") (pintype "bidirectional"))
    )
    (net (code "22") (name "AUX_RED") (class "Default")
      (node (ref "Q2") (pin "1") (pinfunction "G_1") (pintype "passive"))
      (node (ref "TO_MAIN") (pin "3") (pinfunction "3_3") (pintype "bidirectional"))
    )
    (net (code "23") (name "AUX_SCLK") (class "Default")
      (node (ref "TO_MAIN") (pin "2") (pinfunction "2_2") (pintype "bidirectional"))
      (node (ref "U8") (pin "17") (pinfunction "SCK_17") (pintype "bidirectional"))
    )
    (net (code "24") (name "BCLK") (class "Default")
      (node (ref "L6") (pin "1") (pinfunction "1_1") (pintype "passive"))
      (node (ref "U3") (pin "2") (pinfunction "BCLK_2") (pintype "bidirectional"))
    )
    (net (code "25") (name "BLUE") (class "Default")
      (node (ref "TO_AUX") (pin "8") (pinfunction "8_8") (pintype "bidirectional"))
    )
    (net (code "26") (name "CS_CC8531") (class "Default")
      (node (ref "CCD") (pin "5") (pinfunction "5_5") (pintype "bidirectional"))
      (node (ref "U1") (pin "3") (pinfunction "CSN_3") (pintype "bidirectional"))
      (node (ref "U4") (pin "25") (pinfunction "PC2(ADC2)_25") (pintype "bidirectional"))
    )
    (net (code "27") (name "CS_CODEC") (class "Default")
      (node (ref "U3") (pin "9") (pinfunction "SCL/SSZ_9") (pintype "bidirectional"))
      (node (ref "U4") (pin "23") (pinfunction "PC0(ADC0)_23") (pintype "bidirectional"))
    )
    (net (code "28") (name "CS_SD") (class "Default")
      (node (ref "MICROSD") (pin "CD/DAT3") (pinfunction "~{CS}_CD/DAT3") (pintype "bidirectional"))
      (node (ref "U4") (pin "12") (pinfunction "PB0(CLK0)_12") (pintype "bidirectional"))
      (node (ref "U7") (pin "89") (pinfunction "PB18_89") (pintype "bidirectional"))
    )
    (net (code "29") (name "CS_TOUCH") (class "Default")
      (node (ref "TO_AUX") (pin "7") (pinfunction "7_7") (pintype "bidirectional"))
    )
    (net (code "30") (name "CTS") (class "Default")
      (node (ref "SERIAL") (pin "2") (pinfunction "2_2") (pintype "bidirectional"))
    )
    (net (code "31") (name "D+") (class "Default")
      (node (ref "R2") (pin "2") (pinfunction "2_2") (pintype "passive"))
      (node (ref "R7") (pin "2") (pinfunction "2_2") (pintype "passive"))
      (node (ref "USB") (pin "3") (pinfunction "D+_3") (pintype "bidirectional"))
    )
    (net (code "32") (name "DIN") (class "Default")
      (node (ref "L13") (pin "1") (pinfunction "1_1") (pintype "passive"))
      (node (ref "U3") (pin "4") (pinfunction "DIN/MFP1_4") (pintype "bidirectional"))
    )
    (net (code "33") (name "DOUT") (class "Default")
      (node (ref "L11") (pin "1") (pinfunction "1_1") (pintype "passive"))
      (node (ref "U3") (pin "5") (pinfunction "DOUT/MFP2_5") (pintype "bidirectional"))
    )
    (net (code "34") (name "GND") (class "Default")
      (node (ref "AVR") (pin "C") (pinfunction "C_C") (pintype "passive"))
      (node (ref "B1") (pin "-") (pinfunction "N_-") (pintype "passive"))
      (node (ref "B1") (pin "X1") (pinfunction "CASE_X1") (pintype "passive"))
      (node (ref "B1") (pin "X2") (pinfunction "CASE_X2") (pintype "passive"))
      (node (ref "C1") (pin "2") (pinfunction "2_2") (pintype "passive"))
      (node (ref "C10") (pin "2") (pinfunction "2_2") (pintype "passive"))
      (node (ref "C11") (pin "2") (pinfunction "2_2") (pintype "passive"))
      (node (ref "C12") (pin "2") (pinfunction "2_2") (pintype "passive"))
      (node (ref "C13") (pin "2") (pinfunction "2_2") (pintype "passive"))
      (node (ref "C14") (pin "2") (pinfunction "2_2") (pintype "passive"))
      (node (ref "C15") (pin "2") (pinfunction "2_2") (pintype "passive"))
      (node (ref "C16") (pin "2") (pinfunction "2_2") (pintype "passive"))
      (node (ref "C17") (pin "2") (pinfunction "2_2") (pintype "passive"))
      (node (ref "C18") (pin "2") (pinfunction "2_2") (pintype "passive"))
      (node (ref "C19") (pin "2") (pinfunction "2_2") (pintype "passive"))
      (node (ref "C2") (pin "2") (pinfunction "2_2") (pintype "passive"))
      (node (ref "C20") (pin "2") (pinfunction "2_2") (pintype "passive"))
      (node (ref "C21") (pin "2") (pinfunction "2_2") (pintype "passive"))
      (node (ref "C22") (pin "2") (pinfunction "2_2") (pintype "passive"))
      (node (ref "C23") (pin "2") (pinfunction "2_2") (pintype "passive"))
      (node (ref "C24") (pin "2") (pinfunction "2_2") (pintype "passive"))
      (node (ref "C27") (pin "2") (pinfunction "2_2") (pintype "passive"))
      (node (ref "C28") (pin "2") (pinfunction "2_2") (pintype "passive"))
      (node (ref "C29") (pin "2") (pinfunction "2_2") (pintype "passive"))
      (node (ref "C3") (pin "2") (pinfunction "2_2") (pintype "passive"))
      (node (ref "C31") (pin "2") (pinfunction "2_2") (pintype "passive"))
      (node (ref "C32") (pin "2") (pinfunction "2_2") (pintype "passive"))
      (node (ref "C35") (pin "2") (pinfunction "2_2") (pintype "passive"))
      (node (ref "C4") (pin "2") (pinfunction "2_2") (pintype "passive"))
      (node (ref "C40") (pin "2") (pinfunction "2_2") (pintype "passive"))
      (node (ref "C41") (pin "2") (pinfunction "2_2") (pintype "passive"))
      (node (ref "C42") (pin "2") (pinfunction "2_2") (pintype "passive"))
      (node (ref "C43") (pin "2") (pinfunction "2_2") (pintype "passive"))
      (node (ref "C44") (pin "2") (pinfunction "2_2") (pintype "passive"))
      (node (ref "C45") (pin "2") (pinfunction "2_2") (pintype "passive"))
      (node (ref "C46") (pin "2") (pinfunction "2_2") (pintype "passive"))
      (node (ref "C47") (pin "2") (pinfunction "2_2") (pintype "passive"))
      (node (ref "C48") (pin "2") (pinfunction "2_2") (pintype "passive"))
      (node (ref "C49") (pin "2") (pinfunction "2_2") (pintype "passive"))
      (node (ref "C5") (pin "2") (pinfunction "2_2") (pintype "passive"))
      (node (ref "C50") (pin "2") (pinfunction "2_2") (pintype "passive"))
      (node (ref "C51") (pin "2") (pinfunction "2_2") (pintype "passive"))
      (node (ref "C52") (pin "2") (pinfunction "2_2") (pintype "passive"))
      (node (ref "C53") (pin "2") (pinfunction "2_2") (pintype "passive"))
      (node (ref "C54") (pin "2") (pinfunction "2_2") (pintype "passive"))
      (node (ref "C56") (pin "2") (pinfunction "2_2") (pintype "passive"))
      (node (ref "C57") (pin "2") (pinfunction "2_2") (pintype "passive"))
      (node (ref "C6") (pin "2") (pinfunction "2_2") (pintype "passive"))
      (node (ref "C65") (pin "2") (pinfunction "2_2") (pintype "passive"))
      (node (ref "C7") (pin "2") (pinfunction "2_2") (pintype "passive"))
      (node (ref "C8") (pin "2") (pinfunction "2_2") (pintype "passive"))
      (node (ref "C9") (pin "2") (pinfunction "2_2") (pintype "passive"))
      (node (ref "CC8531") (pin "A") (pinfunction "A_A") (pintype "passive"))
      (node (ref "CCD") (pin "1") (pinfunction "1_1") (pintype "bidirectional"))
      (node (ref "ICSP") (pin "6") (pinfunction "6_6") (pintype "bidirectional"))
      (node (ref "L10") (pin "1") (pinfunction "1_1") (pintype "passive"))
      (node (ref "MICROSD") (pin "GND1") (pinfunction "GND_GND1") (pintype "bidirectional"))
      (node (ref "MICROSD") (pin "GND2") (pinfunction "GND_GND2") (pintype "bidirectional"))
      (node (ref "MICROSD") (pin "GND3") (pinfunction "GND_GND3") (pintype "bidirectional"))
      (node (ref "MICROSD") (pin "GND4") (pinfunction "GND_GND4") (pintype "bidirectional"))
      (node (ref "MICROSD") (pin "SWB") (pinfunction "SWB_SWB") (pintype "bidirectional"))
      (node (ref "MICROSD") (pin "VSS") (pinfunction "GND_VSS") (pintype "bidirectional"))
      (node (ref "POWER") (pin "C") (pinfunction "C_C") (pintype "passive"))
      (node (ref "R10") (pin "1") (pinfunction "1_1") (pintype "passive"))
      (node (ref "R17") (pin "1") (pinfunction "1_1") (pintype "passive"))
      (node (ref "R20") (pin "1") (pinfunction "1_1") (pintype "passive"))
      (node (ref "R21") (pin "1") (pinfunction "1_1") (pintype "passive"))
      (node (ref "R4") (pin "1") (pinfunction "1_1") (pintype "passive"))
      (node (ref "R8") (pin "1") (pinfunction "1_1") (pintype "passive"))
      (node (ref "SERIAL") (pin "1") (pinfunction "1_1") (pintype "bidirectional"))
      (node (ref "SMA") (pin "GND1") (pinfunction "GND_GND1") (pintype "bidirectional"))
      (node (ref "SMA") (pin "GND2") (pinfunction "GND_GND2") (pintype "bidirectional"))
      (node (ref "SMA") (pin "GND3") (pinfunction "GND_GND3") (pintype "bidirectional"))
      (node (ref "SMA") (pin "GND4") (pinfunction "GND_GND4") (pintype "bidirectional"))
      (node (ref "TO_AUX") (pin "10") (pinfunction "10_10") (pintype "bidirectional"))
      (node (ref "U1") (pin "29") (pinfunction "VBAT_29") (pintype "bidirectional"))
      (node (ref "U1") (pin "34") (pinfunction "GIO12_34") (pintype "bidirectional"))
      (node (ref "U1") (pin "35") (pinfunction "GIO13_35") (pintype "bidirectional"))
      (node (ref "U1") (pin "8") (pinfunction "GIO2_8") (pintype "bidirectional"))
      (node (ref "U1") (pin "GND") (pinfunction "GND_GND") (pintype "bidirectional"))
      (node (ref "U2") (pin "12") (pinfunction "GND_12") (pintype "bidirectional"))
      (node (ref "U2") (pin "14") (pinfunction "GND_14") (pintype "bidirectional"))
      (node (ref "U2") (pin "8") (pinfunction "GND_8") (pintype "bidirectional"))
      (node (ref "U2") (pin "9") (pinfunction "GND_9") (pintype "bidirectional"))
      (node (ref "U2") (pin "GND") (pinfunction "GND_GND") (pintype "bidirectional"))
      (node (ref "U3") (pin "28") (pinfunction "DVSS_28") (pintype "bidirectional"))
      (node (ref "U3") (pin "7") (pinfunction "IOVSS_7") (pintype "bidirectional"))
      (node (ref "U3") (pin "GND") (pinfunction "GND_GND") (pintype "bidirectional"))
      (node (ref "U4") (pin "21") (pinfunction "GND3_21") (pintype "bidirectional"))
      (node (ref "U4") (pin "3") (pinfunction "GND1_3") (pintype "bidirectional"))
      (node (ref "U4") (pin "5") (pinfunction "GND2_5") (pintype "bidirectional"))
      (node (ref "U5") (pin "2") (pinfunction "GND_2") (pintype "bidirectional"))
      (node (ref "U5") (pin "4") (pinfunction "GND_4") (pintype "bidirectional"))
      (node (ref "U6") (pin "1") (pinfunction "NTC_1") (pintype "bidirectional"))
      (node (ref "U6") (pin "14") (pinfunction "D1_14") (pintype "bidirectional"))
      (node (ref "U6") (pin "4") (pinfunction "D2_4") (pintype "bidirectional"))
      (node (ref "U6") (pin "GND") (pinfunction "GND_GND") (pintype "bidirectional"))
      (node (ref "USB") (pin "5") (pinfunction "GND_5") (pintype "bidirectional"))
      (node (ref "USB") (pin "GND1") (pinfunction "GND_GND1") (pintype "bidirectional"))
      (node (ref "USB") (pin "GND2") (pinfunction "GND_GND2") (pintype "bidirectional"))
      (node (ref "USB") (pin "GND3") (pinfunction "GND_GND3") (pintype "bidirectional"))
      (node (ref "USB") (pin "GND4") (pinfunction "GND_GND4") (pintype "bidirectional"))
      (node (ref "X1") (pin "2") (pinfunction "CASE_2") (pintype "passive"))
      (node (ref "X1") (pin "4") (pinfunction "CASE_4") (pintype "passive"))
      (node (ref "X2") (pin "2") (pinfunction "CASE_2") (pintype "passive"))
      (node (ref "X2") (pin "4") (pinfunction "CASE_4") (pintype "passive"))
      (node (ref "X3") (pin "GND-1") (pinfunction "CASE_GND-1") (pintype "passive"))
      (node (ref "X3") (pin "GND-2") (pinfunction "CASE_GND-2") (pintype "passive"))
    )
    (net (code "35") (name "GREEN") (class "Default")
      (node (ref "TO_AUX") (pin "6") (pinfunction "6_6") (pintype "bidirectional"))
    )
    (net (code "36") (name "IN_L") (class "Default")
      (node (ref "LINE_IN") (pin "4") (pinfunction "L_4") (pintype "bidirectional"))
      (node (ref "R23") (pin "2") (pinfunction "2_2") (pintype "passive"))
    )
    (net (code "37") (name "IN_R") (class "Default")
      (node (ref "LINE_IN") (pin "1") (pinfunction "R_1") (pintype "bidirectional"))
    )
    (net (code "38") (name "LINEIN_SENSE") (class "Default")
      (node (ref "LINE_IN") (pin "3") (pinfunction "L_SW_3") (pintype "bidirectional"))
      (node (ref "R22") (pin "1") (pinfunction "1_1") (pintype "passive"))
    )
    (net (code "39") (name "LINE_L") (class "Default")
      (node (ref "R27") (pin "1") (pinfunction "1_1") (pintype "passive"))
      (node (ref "U3") (pin "22") (pinfunction "LOL_22") (pintype "bidirectional"))
    )
    (net (code "40") (name "LINE_R") (class "Default")
      (node (ref "R29") (pin "1") (pinfunction "1_1") (pintype "passive"))
      (node (ref "U3") (pin "23") (pinfunction "LOR_23") (pintype "bidirectional"))
    )
    (net (code "41") (name "LNA_EN") (class "Default")
      (node (ref "U1") (pin "38") (pinfunction "XLNAEN_38") (pintype "bidirectional"))
      (node (ref "U2") (pin "6") (pinfunction "EN_6") (pintype "bidirectional"))
    )
    (net (code "42") (name "MCLK") (class "Default")
      (node (ref "L5") (pin "1") (pinfunction "1_1") (pintype "passive"))
      (node (ref "U3") (pin "1") (pinfunction "MCLK_1") (pintype "bidirectional"))
    )
    (net (code "43") (name "MISO") (class "Default")
      (node (ref "CCD") (pin "10") (pinfunction "10_10") (pintype "bidirectional"))
      (node (ref "ICSP") (pin "1") (pinfunction "1_1") (pintype "bidirectional"))
      (node (ref "TO_AUX") (pin "3") (pinfunction "3_3") (pintype "bidirectional"))
      (node (ref "U1") (pin "6") (pinfunction "MISO_6") (pintype "bidirectional"))
      (node (ref "U3") (pin "11") (pinfunction "MISO/MFP4_11") (pintype "bidirectional"))
      (node (ref "U4") (pin "16") (pinfunction "PB4(MISO)_16") (pintype "bidirectional"))
      (node (ref "U7") (pin "108") (pinfunction "PA25_108") (pintype "bidirectional"))
    )
    (net (code "44") (name "MISO_SD") (class "Default")
      (node (ref "MICROSD") (pin "DAT0") (pinfunction "MISO_DAT0") (pintype "bidirectional"))
      (node (ref "U4") (pin "9") (pinfunction "PD5_9") (pintype "bidirectional"))
      (node (ref "U7") (pin "92") (pinfunction "PB21_92") (pintype "bidirectional"))
    )
    (net (code "45") (name "MOSI") (class "Default")
      (node (ref "CCD") (pin "8") (pinfunction "8_8") (pintype "bidirectional"))
      (node (ref "ICSP") (pin "4") (pinfunction "4_4") (pintype "bidirectional"))
      (node (ref "TO_AUX") (pin "5") (pinfunction "5_5") (pintype "bidirectional"))
      (node (ref "U1") (pin "5") (pinfunction "MOSI_5") (pintype "bidirectional"))
      (node (ref "U3") (pin "10") (pinfunction "SDA/MOSI_10") (pintype "bidirectional"))
      (node (ref "U4") (pin "15") (pinfunction "PB3(MOSI)_15") (pintype "bidirectional"))
      (node (ref "U7") (pin "109") (pinfunction "PA26_109") (pintype "bidirectional"))
    )
    (net (code "46") (name "MOSI_SD") (class "Default")
      (node (ref "MICROSD") (pin "CMD") (pinfunction "MOSI_CMD") (pintype "bidirectional"))
      (node (ref "U4") (pin "11") (pinfunction "PD7(AIN1)_11") (pintype "bidirectional"))
      (node (ref "U7") (pin "90") (pinfunction "PB19_90") (pintype "bidirectional"))
    )
    (net (code "47") (name "Net-(AVR-PadA)") (class "Default")
      (node (ref "AVR") (pin "A") (pinfunction "A_A") (pintype "passive"))
      (node (ref "R14") (pin "1") (pinfunction "1_1") (pintype "passive"))
    )
    (net (code "48") (name "Net-(B1-P)") (class "Default")
      (node (ref "B1") (pin "+") (pinfunction "P_+") (pintype "passive"))
      (node (ref "Q1") (pin "2") (pinfunction "S_2") (pintype "passive"))
      (node (ref "U6") (pin "9") (pinfunction "BAT_9") (pintype "bidirectional"))
    )
    (net (code "49") (name "Net-(C25-Pad1)") (class "Default")
      (node (ref "C25") (pin "1") (pinfunction "1_1") (pintype "passive"))
      (node (ref "L8") (pin "2") (pinfunction "2_2") (pintype "passive"))
    )
    (net (code "50") (name "Net-(C25-Pad2)") (class "Default")
      (node (ref "C25") (pin "2") (pinfunction "2_2") (pintype "passive"))
      (node (ref "C26") (pin "1") (pinfunction "1_1") (pintype "passive"))
      (node (ref "C28") (pin "1") (pinfunction "1_1") (pintype "passive"))
      (node (ref "L10") (pin "2") (pinfunction "2_2") (pintype "passive"))
    )
    (net (code "51") (name "Net-(C26-Pad2)") (class "Default")
      (node (ref "C26") (pin "2") (pinfunction "2_2") (pintype "passive"))
      (node (ref "SMA") (pin "SIG") (pinfunction "SIG_SIG") (pintype "bidirectional"))
    )
    (net (code "52") (name "Net-(C27-Pad1)") (class "Default")
      (node (ref "C27") (pin "1") (pinfunction "1_1") (pintype "passive"))
      (node (ref "L7") (pin "2") (pinfunction "2_2") (pintype "passive"))
      (node (ref "L8") (pin "1") (pinfunction "1_1") (pintype "passive"))
    )
    (net (code "53") (name "Net-(C54-Pad1)") (class "Default")
      (node (ref "C54") (pin "1") (pinfunction "1_1") (pintype "passive"))
      (node (ref "R19") (pin "1") (pinfunction "1_1") (pintype "passive"))
    )
    (net (code "54") (name "Net-(C65-Pad1)") (class "Default")
      (node (ref "C65") (pin "1") (pinfunction "1_1") (pintype "passive"))
      (node (ref "L18") (pin "1") (pinfunction "1_1") (pintype "passive"))
      (node (ref "TO_AUX") (pin "2") (pinfunction "2_2") (pintype "bidirectional"))
    )
    (net (code "55") (name "Net-(CC8531-PadC)") (class "Default")
      (node (ref "CC8531") (pin "C") (pinfunction "C_C") (pintype "passive"))
      (node (ref "R5") (pin "2") (pinfunction "2_2") (pintype "passive"))
    )
    (net (code "56") (name "Net-(CCD-Pad9)") (class "Default")
      (node (ref "CCD") (pin "9") (pinfunction "9_9") (pintype "bidirectional"))
      (node (ref "EXT") (pin "1") (pinfunction "1_1") (pintype "passive"))
    )
    (net (code "57") (name "Net-(CHARGE-PadA)") (class "Default")
      (node (ref "CHARGE") (pin "A") (pinfunction "A_A") (pintype "passive"))
      (node (ref "R18") (pin "1") (pinfunction "1_1") (pintype "passive"))
    )
    (net (code "58") (name "Net-(D1-C1)") (class "Default")
      (node (ref "D1") (pin "3") (pinfunction "C1_3") (pintype "passive"))
      (node (ref "L16") (pin "2") (pinfunction "2_2") (pintype "passive"))
    )
    (net (code "59") (name "Net-(POWER-PadA)") (class "Default")
      (node (ref "POWER") (pin "A") (pinfunction "A_A") (pintype "passive"))
      (node (ref "R3") (pin "1") (pinfunction "1_1") (pintype "passive"))
    )
    (net (code "60") (name "Net-(Q1-D)") (class "Default")
      (node (ref "C52") (pin "1") (pinfunction "1_1") (pintype "passive"))
      (node (ref "F1") (pin "1") (pinfunction "1_1") (pintype "passive"))
      (node (ref "L17") (pin "2") (pinfunction "2_2") (pintype "passive"))
      (node (ref "Q1") (pin "3") (pinfunction "D_3") (pintype "passive"))
      (node (ref "U6") (pin "10") (pinfunction "VOUT_10") (pintype "bidirectional"))
      (node (ref "U6") (pin "3") (pinfunction "VOUTS_3") (pintype "bidirectional"))
    )
    (net (code "61") (name "Net-(Q1-G)") (class "Default")
      (node (ref "Q1") (pin "1") (pinfunction "G_1") (pintype "passive"))
      (node (ref "U6") (pin "8") (pinfunction "GATE_8") (pintype "bidirectional"))
    )
    (net (code "62") (name "Net-(Q2-D)") (class "Default")
      (node (ref "LED1") (pin "1") (pinfunction "KR_1") (pintype "passive"))
      (node (ref "LED1") (pin "1-2") (pinfunction "KR_1-2") (pintype "passive"))
      (node (ref "LED2") (pin "1") (pinfunction "KR_1") (pintype "passive"))
      (node (ref "LED2") (pin "1-2") (pinfunction "KR_1-2") (pintype "passive"))
      (node (ref "LED3") (pin "1") (pinfunction "KR_1") (pintype "passive"))
      (node (ref "LED3") (pin "1-2") (pinfunction "KR_1-2") (pintype "passive"))
      (node (ref "LED4") (pin "1") (pinfunction "KR_1") (pintype "passive"))
      (node (ref "LED4") (pin "1-2") (pinfunction "KR_1-2") (pintype "passive"))
      (node (ref "Q2") (pin "3") (pinfunction "D_3") (pintype "passive"))
    )
    (net (code "63") (name "Net-(Q3-D)") (class "Default")
      (node (ref "LED1") (pin "4") (pinfunction "KG_4") (pintype "passive"))
      (node (ref "LED1") (pin "4-2") (pinfunction "KG_4-2") (pintype "passive"))
      (node (ref "LED2") (pin "4") (pinfunction "KG_4") (pintype "passive"))
      (node (ref "LED2") (pin "4-2") (pinfunction "KG_4-2") (pintype "passive"))
      (node (ref "LED3") (pin "4") (pinfunction "KG_4") (pintype "passive"))
      (node (ref "LED3") (pin "4-2") (pinfunction "KG_4-2") (pintype "passive"))
      (node (ref "LED4") (pin "4") (pinfunction "KG_4") (pintype "passive"))
      (node (ref "LED4") (pin "4-2") (pinfunction "KG_4-2") (pintype "passive"))
      (node (ref "Q3") (pin "3") (pinfunction "D_3") (pintype "passive"))
    )
    (net (code "64") (name "Net-(Q4-D)") (class "Default")
      (node (ref "LED1") (pin "3") (pinfunction "KB_3") (pintype "passive"))
      (node (ref "LED1") (pin "3-2") (pinfunction "KB_3-2") (pintype "passive"))
      (node (ref "LED2") (pin "3") (pinfunction "KB_3") (pintype "passive"))
      (node (ref "LED2") (pin "3-2") (pinfunction "KB_3-2") (pintype "passive"))
      (node (ref "LED3") (pin "3") (pinfunction "KB_3") (pintype "passive"))
      (node (ref "LED3") (pin "3-2") (pinfunction "KB_3-2") (pintype "passive"))
      (node (ref "LED4") (pin "3") (pinfunction "KB_3") (pintype "passive"))
      (node (ref "LED4") (pin "3-2") (pinfunction "KB_3-2") (pintype "passive"))
      (node (ref "Q4") (pin "3") (pinfunction "D_3") (pintype "passive"))
    )
    (net (code "65") (name "Net-(R13-Pad2)") (class "Default")
      (node (ref "R13") (pin "2") (pinfunction "2_2") (pintype "passive"))
      (node (ref "R27") (pin "2") (pinfunction "2_2") (pintype "passive"))
      (node (ref "R28") (pin "2") (pinfunction "2_2") (pintype "passive"))
    )
    (net (code "66") (name "Net-(R16-Pad2)") (class "Default")
      (node (ref "R16") (pin "2") (pinfunction "2_2") (pintype "passive"))
      (node (ref "R29") (pin "2") (pinfunction "2_2") (pintype "passive"))
      (node (ref "R30") (pin "2") (pinfunction "2_2") (pintype "passive"))
    )
    (net (code "67") (name "Net-(R26-Pad2)") (class "Default")
      (node (ref "R26") (pin "2") (pinfunction "2_2") (pintype "passive"))
      (node (ref "SW1") (pin "P$1") (pinfunction "P$1_P$1") (pintype "bidirectional"))
    )
    (net (code "68") (name "Net-(R33-Pad2)") (class "Default")
      (node (ref "R33") (pin "2") (pinfunction "2_2") (pintype "passive"))
      (node (ref "SW4") (pin "P$1") (pinfunction "P$1_P$1") (pintype "bidirectional"))
    )
    (net (code "69") (name "Net-(R34-Pad2)") (class "Default")
      (node (ref "R34") (pin "2") (pinfunction "2_2") (pintype "passive"))
      (node (ref "SW5") (pin "P$1") (pinfunction "P$1_P$1") (pintype "bidirectional"))
    )
    (net (code "70") (name "Net-(R35-Pad2)") (class "Default")
      (node (ref "R35") (pin "2") (pinfunction "2_2") (pintype "passive"))
      (node (ref "SW6") (pin "P$1") (pinfunction "P$1_P$1") (pintype "bidirectional"))
    )
    (net (code "71") (name "Net-(R37-Pad2)") (class "Default")
      (node (ref "R37") (pin "2") (pinfunction "2_2") (pintype "passive"))
      (node (ref "SW7") (pin "P$1") (pinfunction "P$1_P$1") (pintype "bidirectional"))
    )
    (net (code "72") (name "Net-(R38-Pad2)") (class "Default")
      (node (ref "R38") (pin "2") (pinfunction "2_2") (pintype "passive"))
      (node (ref "SW8") (pin "P$1") (pinfunction "P$1_P$1") (pintype "bidirectional"))
    )
    (net (code "73") (name "Net-(R39-Pad2)") (class "Default")
      (node (ref "R39") (pin "2") (pinfunction "2_2") (pintype "passive"))
      (node (ref "SW9") (pin "P$1") (pinfunction "P$1_P$1") (pintype "bidirectional"))
    )
    (net (code "74") (name "Net-(R40-Pad2)") (class "Default")
      (node (ref "R40") (pin "2") (pinfunction "2_2") (pintype "passive"))
      (node (ref "SW10") (pin "P$1") (pinfunction "P$1_P$1") (pintype "bidirectional"))
    )
    (net (code "75") (name "Net-(U$15-BYPASS)") (class "Default")
      (node (ref "C33") (pin "1") (pinfunction "1_1") (pintype "passive"))
      (node (ref "U$15") (pin "1") (pinfunction "BYPASS_1") (pintype "bidirectional"))
    )
    (net (code "76") (name "Net-(U$15-INA)") (class "Default")
      (node (ref "R12") (pin "2") (pinfunction "2_2") (pintype "passive"))
      (node (ref "R13") (pin "1") (pinfunction "1_1") (pintype "passive"))
      (node (ref "U$15") (pin "8") (pinfunction "INA_8") (pintype "bidirectional"))
    )
    (net (code "77") (name "Net-(U$15-INB)") (class "Default")
      (node (ref "R15") (pin "2") (pinfunction "2_2") (pintype "passive"))
      (node (ref "R16") (pin "1") (pinfunction "1_1") (pintype "passive"))
      (node (ref "U$15") (pin "4") (pinfunction "INB_4") (pintype "bidirectional"))
    )
    (net (code "78") (name "Net-(U$15-OUTA)") (class "Default")
      (node (ref "C36") (pin "1") (pinfunction "1_1") (pintype "passive"))
      (node (ref "R12") (pin "1") (pinfunction "1_1") (pintype "passive"))
      (node (ref "U$15") (pin "7") (pinfunction "OUTA_7") (pintype "bidirectional"))
    )
    (net (code "79") (name "Net-(U$15-OUTB)") (class "Default")
      (node (ref "C39") (pin "1") (pinfunction "1_1") (pintype "passive"))
      (node (ref "R15") (pin "1") (pinfunction "1_1") (pintype "passive"))
      (node (ref "U$15") (pin "5") (pinfunction "OUTB_5") (pintype "bidirectional"))
    )
    (net (code "80") (name "Net-(U$15-SHUTDOWN)") (class "Default")
      (node (ref "R31") (pin "1") (pinfunction "1_1") (pintype "passive"))
      (node (ref "U$15") (pin "3") (pinfunction "SHUTDOWN_3") (pintype "bidirectional"))
    )
    (net (code "81") (name "Net-(U1-AD0{slash}GIO7)") (class "Default")
      (node (ref "L11") (pin "2") (pinfunction "2_2") (pintype "passive"))
      (node (ref "U1") (pin "16") (pinfunction "AD0/GIO7_16") (pintype "bidirectional"))
    )
    (net (code "82") (name "Net-(U1-AD1{slash}GIO8)") (class "Default")
      (node (ref "L13") (pin "2") (pinfunction "2_2") (pintype "passive"))
      (node (ref "U1") (pin "17") (pinfunction "AD1/GIO8_17") (pintype "bidirectional"))
    )
    (net (code "83") (name "Net-(U1-AD2{slash}GIO9)") (class "Default")
      (node (ref "R7") (pin "1") (pinfunction "1_1") (pintype "passive"))
      (node (ref "U1") (pin "19") (pinfunction "AD2/GIO9_19") (pintype "bidirectional"))
    )
    (net (code "84") (name "Net-(U1-BCLK{slash}GIO5)") (class "Default")
      (node (ref "L6") (pin "2") (pinfunction "2_2") (pintype "passive"))
      (node (ref "U1") (pin "14") (pinfunction "BCLK/GIO5_14") (pintype "bidirectional"))
    )
    (net (code "85") (name "Net-(U1-DCPL)") (class "Default")
      (node (ref "C23") (pin "1") (pinfunction "1_1") (pintype "passive"))
      (node (ref "U1") (pin "39") (pinfunction "DCPL_39") (pintype "bidirectional"))
    )
    (net (code "86") (name "Net-(U1-GIO3)") (class "Default")
      (node (ref "R5") (pin "1") (pinfunction "1_1") (pintype "passive"))
      (node (ref "U1") (pin "9") (pinfunction "GIO3_9") (pintype "bidirectional"))
    )
    (net (code "87") (name "Net-(U1-MCLK{slash}GIO4)") (class "Default")
      (node (ref "L5") (pin "2") (pinfunction "2_2") (pintype "passive"))
      (node (ref "U1") (pin "13") (pinfunction "MCLK/GIO4_13") (pintype "bidirectional"))
    )
    (net (code "88") (name "Net-(U1-RBIAS)") (class "Default")
      (node (ref "R4") (pin "2") (pinfunction "2_2") (pintype "passive"))
      (node (ref "U1") (pin "30") (pinfunction "RBIAS_30") (pintype "bidirectional"))
    )
    (net (code "89") (name "Net-(U1-RSTN)") (class "Default")
      (node (ref "L4") (pin "1") (pinfunction "1_1") (pintype "passive"))
      (node (ref "U1") (pin "11") (pinfunction "RSTN_11") (pintype "bidirectional"))
    )
    (net (code "90") (name "Net-(U1-USBN)") (class "Default")
      (node (ref "C14") (pin "1") (pinfunction "1_1") (pintype "passive"))
      (node (ref "R1") (pin "1") (pinfunction "1_1") (pintype "passive"))
      (node (ref "U1") (pin "1") (pinfunction "USBN_1") (pintype "bidirectional"))
    )
    (net (code "91") (name "Net-(U1-USBP)") (class "Default")
      (node (ref "C13") (pin "1") (pinfunction "1_1") (pintype "passive"))
      (node (ref "R2") (pin "1") (pinfunction "1_1") (pintype "passive"))
      (node (ref "U1") (pin "2") (pinfunction "USBP_2") (pintype "bidirectional"))
    )
    (net (code "92") (name "Net-(U1-WCLK{slash}GIO6)") (class "Default")
      (node (ref "L9") (pin "2") (pinfunction "2_2") (pintype "passive"))
      (node (ref "U1") (pin "15") (pinfunction "WCLK/GIO6_15") (pintype "bidirectional"))
    )
    (net (code "93") (name "Net-(U1-X0)") (class "Default")
      (node (ref "C24") (pin "1") (pinfunction "1_1") (pintype "passive"))
      (node (ref "U1") (pin "22") (pinfunction "X0_22") (pintype "bidirectional"))
      (node (ref "X1") (pin "3") (pinfunction "2_3") (pintype "passive"))
    )
    (net (code "94") (name "Net-(U1-X1)") (class "Default")
      (node (ref "C29") (pin "1") (pinfunction "1_1") (pintype "passive"))
      (node (ref "U1") (pin "21") (pinfunction "X1_21") (pintype "bidirectional"))
      (node (ref "X1") (pin "1") (pinfunction "1_1") (pintype "passive"))
    )
    (net (code "95") (name "Net-(U1-XPAEN)") (class "Default")
      (node (ref "L12") (pin "1") (pinfunction "1_1") (pintype "passive"))
      (node (ref "U1") (pin "36") (pinfunction "XPAEN_36") (pintype "bidirectional"))
    )
    (net (code "96") (name "Net-(U2-ANT)") (class "Default")
      (node (ref "L7") (pin "1") (pinfunction "1_1") (pintype "passive"))
      (node (ref "U2") (pin "11") (pinfunction "ANT_11") (pintype "bidirectional"))
    )
    (net (code "97") (name "Net-(U2-BIAS)") (class "Default")
      (node (ref "R8") (pin "2") (pinfunction "2_2") (pintype "passive"))
      (node (ref "U2") (pin "15") (pinfunction "BIAS_15") (pintype "bidirectional"))
    )
    (net (code "98") (name "Net-(U2-HGM)") (class "Default")
      (node (ref "R9") (pin "1") (pinfunction "1_1") (pintype "passive"))
      (node (ref "U2") (pin "7") (pinfunction "HGM_7") (pintype "bidirectional"))
    )
    (net (code "99") (name "Net-(U3-AVDD)") (class "Default")
      (node (ref "C48") (pin "1") (pinfunction "1_1") (pintype "passive"))
      (node (ref "U3") (pin "24") (pinfunction "AVDD_24") (pintype "bidirectional"))
    )
    (net (code "100") (name "Net-(U3-DVDD)") (class "Default")
      (node (ref "C49") (pin "1") (pinfunction "1_1") (pintype "passive"))
      (node (ref "U3") (pin "29") (pinfunction "DVDD_29") (pintype "bidirectional"))
    )
    (net (code "101") (name "Net-(U3-IN1_L)") (class "Default")
      (node (ref "C38") (pin "2") (pinfunction "2_2") (pintype "passive"))
      (node (ref "U3") (pin "13") (pinfunction "IN1_L_13") (pintype "bidirectional"))
    )
    (net (code "102") (name "Net-(U3-IN1_R)") (class "Default")
      (node (ref "C37") (pin "2") (pinfunction "2_2") (pintype "passive"))
      (node (ref "U3") (pin "14") (pinfunction "IN1_R_14") (pintype "bidirectional"))
    )
    (net (code "103") (name "Net-(U3-REF)") (class "Default")
      (node (ref "C50") (pin "1") (pinfunction "1_1") (pintype "passive"))
      (node (ref "U3") (pin "18") (pinfunction "REF_18") (pintype "bidirectional"))
    )
    (net (code "104") (name "Net-(U4-PB6(XTAL1))") (class "Default")
      (node (ref "C46") (pin "1") (pinfunction "1_1") (pintype "passive"))
      (node (ref "U4") (pin "7") (pinfunction "PB6(XTAL1)_7") (pintype "bidirectional"))
      (node (ref "X2") (pin "1") (pinfunction "1_1") (pintype "passive"))
    )
    (net (code "105") (name "Net-(U4-PB7(XTAL2))") (class "Default")
      (node (ref "C47") (pin "1") (pinfunction "1_1") (pintype "passive"))
      (node (ref "U4") (pin "8") (pinfunction "PB7(XTAL2)_8") (pintype "bidirectional"))
      (node (ref "X2") (pin "3") (pinfunction "2_3") (pintype "passive"))
    )
    (net (code "106") (name "Net-(U4-PD3)") (class "Default")
      (node (ref "R14") (pin "2") (pinfunction "2_2") (pintype "passive"))
      (node (ref "U4") (pin "1") (pinfunction "PD3_1") (pintype "bidirectional"))
    )
    (net (code "107") (name "Net-(U5-VIN)") (class "Default")
      (node (ref "F1") (pin "2") (pinfunction "2_2") (pintype "passive"))
      (node (ref "U5") (pin "1") (pinfunction "VIN_1") (pintype "bidirectional"))
    )
    (net (code "108") (name "Net-(U6-CLRPROG)") (class "Default")
      (node (ref "R19") (pin "2") (pinfunction "2_2") (pintype "passive"))
      (node (ref "R20") (pin "2") (pinfunction "2_2") (pintype "passive"))
      (node (ref "U6") (pin "2") (pinfunction "CLRPROG_2") (pintype "bidirectional"))
    )
    (net (code "109") (name "Net-(U6-C{slash}X)") (class "Default")
      (node (ref "R21") (pin "2") (pinfunction "2_2") (pintype "passive"))
      (node (ref "U6") (pin "5") (pinfunction "C/X_5") (pintype "bidirectional"))
      (node (ref "U6") (pin "6") (pinfunction "PROG_6") (pintype "bidirectional"))
    )
    (net (code "110") (name "Net-(U6-D0)") (class "Default")
      (node (ref "C51") (pin "1") (pinfunction "1_1") (pintype "passive"))
      (node (ref "R18") (pin "2") (pinfunction "2_2") (pintype "passive"))
      (node (ref "U6") (pin "11") (pinfunction "VBUS_11") (pintype "bidirectional"))
      (node (ref "U6") (pin "13") (pinfunction "D0_13") (pintype "bidirectional"))
      (node (ref "V_CHRG") (pin "2") (pinfunction "2_2") (pintype "passive"))
    )
    (net (code "111") (name "Net-(U6-SW)") (class "Default")
      (node (ref "L17") (pin "1") (pinfunction "1_1") (pintype "passive"))
      (node (ref "U6") (pin "12") (pinfunction "SW_12") (pintype "bidirectional"))
    )
    (net (code "112") (name "Net-(U6-~{CHRG})") (class "Default")
      (node (ref "CHARGE") (pin "C") (pinfunction "C_C") (pintype "passive"))
      (node (ref "U6") (pin "7") (pinfunction "~{CHRG}_7") (pintype "bidirectional"))
    )
    (net (code "113") (name "Net-(U7E-VDDBU)") (class "Default")
      (node (ref "U7") (pin "41") (pinfunction "VDDUTMI_41") (pintype "bidirectional"))
      (node (ref "U7") (pin "52") (pinfunction "VDDBU_52") (pintype "bidirectional"))
    )
    (net (code "114") (name "Net-(U7E-VDDCORE_1)") (class "Default")
      (node (ref "U7") (pin "10") (pinfunction "VDDCORE_1_10") (pintype "bidirectional"))
      (node (ref "U7") (pin "104") (pinfunction "VDDCORE_4_104") (pintype "bidirectional"))
      (node (ref "U7") (pin "124") (pinfunction "VDDCORE_5_124") (pintype "bidirectional"))
      (node (ref "U7") (pin "34") (pinfunction "VDDPLL_34") (pintype "bidirectional"))
      (node (ref "U7") (pin "45") (pinfunction "VDDCORE_2_45") (pintype "bidirectional"))
      (node (ref "U7") (pin "56") (pinfunction "VDDOUT_56") (pintype "bidirectional"))
      (node (ref "U7") (pin "61") (pinfunction "VDDCORE_3_61") (pintype "bidirectional"))
    )
    (net (code "115") (name "Net-(U7E-VDDIN)") (class "Default")
      (node (ref "U7") (pin "105") (pinfunction "VDDIO_3_105") (pintype "bidirectional"))
      (node (ref "U7") (pin "11") (pinfunction "VDDIO_1_11") (pintype "bidirectional"))
      (node (ref "U7") (pin "125") (pinfunction "VDDIO_4_125") (pintype "bidirectional"))
      (node (ref "U7") (pin "57") (pinfunction "VDDIN_57") (pintype "bidirectional"))
      (node (ref "U7") (pin "62") (pinfunction "VDDIO_2_62") (pintype "bidirectional"))
    )
    (net (code "116") (name "Net-(U7F-XIN)") (class "Default")
      (node (ref "C56") (pin "1") (pinfunction "1_1") (pintype "passive"))
      (node (ref "U7") (pin "36") (pinfunction "XIN_36") (pintype "bidirectional"))
      (node (ref "X3") (pin "X2") (pinfunction "2_X2") (pintype "passive"))
    )
    (net (code "117") (name "Net-(U7F-XOUT)") (class "Default")
      (node (ref "C57") (pin "1") (pinfunction "1_1") (pintype "passive"))
      (node (ref "U7") (pin "35") (pinfunction "XOUT_35") (pintype "bidirectional"))
      (node (ref "X3") (pin "X1") (pinfunction "1_X1") (pintype "passive"))
    )
    (net (code "118") (name "Net-(U8-SNS3)") (class "Default")
      (node (ref "C58") (pin "1") (pinfunction "1_1") (pintype "passive"))
      (node (ref "U8") (pin "8") (pinfunction "SNS3_8") (pintype "bidirectional"))
    )
    (net (code "119") (name "Net-(U8-SNS3K)") (class "Default")
      (node (ref "C58") (pin "2") (pinfunction "2_2") (pintype "passive"))
      (node (ref "R33") (pin "1") (pinfunction "1_1") (pintype "passive"))
      (node (ref "U8") (pin "9") (pinfunction "SNS3K_9") (pintype "bidirectional"))
    )
    (net (code "120") (name "Net-(U8-SNS4)") (class "Default")
      (node (ref "C59") (pin "1") (pinfunction "1_1") (pintype "passive"))
      (node (ref "U8") (pin "10") (pinfunction "SNS4_10") (pintype "bidirectional"))
    )
    (net (code "121") (name "Net-(U8-SNS4K)") (class "Default")
      (node (ref "C59") (pin "2") (pinfunction "2_2") (pintype "passive"))
      (node (ref "R34") (pin "1") (pinfunction "1_1") (pintype "passive"))
      (node (ref "U8") (pin "11") (pinfunction "SNS4K_11") (pintype "bidirectional"))
    )
    (net (code "122") (name "Net-(U8-SNS5)") (class "Default")
      (node (ref "C60") (pin "1") (pinfunction "1_1") (pintype "passive"))
      (node (ref "U8") (pin "12") (pinfunction "SNS5_12") (pintype "bidirectional"))
    )
    (net (code "123") (name "Net-(U8-SNS5K)") (class "Default")
      (node (ref "C60") (pin "2") (pinfunction "2_2") (pintype "passive"))
      (node (ref "R35") (pin "1") (pinfunction "1_1") (pintype "passive"))
      (node (ref "U8") (pin "13") (pinfunction "SNS5K_13") (pintype "bidirectional"))
    )
    (net (code "124") (name "Net-(U8-SNS6)") (class "Default")
      (node (ref "C61") (pin "1") (pinfunction "1_1") (pintype "passive"))
      (node (ref "U8") (pin "20") (pinfunction "SNS6_20") (pintype "bidirectional"))
    )
    (net (code "125") (name "Net-(U8-SNS6K)") (class "Default")
      (node (ref "C61") (pin "2") (pinfunction "2_2") (pintype "passive"))
      (node (ref "R37") (pin "1") (pinfunction "1_1") (pintype "passive"))
      (node (ref "U8") (pin "19") (pinfunction "SNS6K_19") (pintype "bidirectional"))
    )
    (net (code "126") (name "Net-(U8-SNS7K{slash}DETECT0)") (class "Default")
      (node (ref "C62") (pin "2") (pinfunction "2_2") (pintype "passive"))
      (node (ref "R38") (pin "1") (pinfunction "1_1") (pintype "passive"))
      (node (ref "U8") (pin "22") (pinfunction "SNS7K/DETECT0_22") (pintype "bidirectional"))
    )
    (net (code "127") (name "Net-(U8-SNS7{slash}DETECT1)") (class "Default")
      (node (ref "C62") (pin "1") (pinfunction "1_1") (pintype "passive"))
      (node (ref "U8") (pin "23") (pinfunction "SNS7/DETECT1_23") (pintype "bidirectional"))
    )
    (net (code "128") (name "Net-(U8-SNS8K{slash}DETECT3)") (class "Default")
      (node (ref "C66") (pin "2") (pinfunction "2_2") (pintype "passive"))
      (node (ref "R39") (pin "1") (pinfunction "1_1") (pintype "passive"))
      (node (ref "U8") (pin "25") (pinfunction "SNS8K/DETECT3_25") (pintype "bidirectional"))
    )
    (net (code "129") (name "Net-(U8-SNS8{slash}DETECT2)") (class "Default")
      (node (ref "C66") (pin "1") (pinfunction "1_1") (pintype "passive"))
      (node (ref "U8") (pin "24") (pinfunction "SNS8/DETECT2_24") (pintype "bidirectional"))
    )
    (net (code "130") (name "Net-(U8-SNS9K{slash}DETECT5)") (class "Default")
      (node (ref "C67") (pin "2") (pinfunction "2_2") (pintype "passive"))
      (node (ref "R40") (pin "1") (pinfunction "1_1") (pintype "passive"))
      (node (ref "U8") (pin "27") (pinfunction "SNS9K/DETECT5_27") (pintype "bidirectional"))
    )
    (net (code "131") (name "Net-(U8-SNS9{slash}DETECT4)") (class "Default")
      (node (ref "C67") (pin "1") (pinfunction "1_1") (pintype "passive"))
      (node (ref "U8") (pin "26") (pinfunction "SNS9/DETECT4_26") (pintype "bidirectional"))
    )
    (net (code "132") (name "Net-(U8-SNS10K{slash}SYNC)") (class "Default")
      (node (ref "C55") (pin "2") (pinfunction "2_2") (pintype "passive"))
      (node (ref "R26") (pin "1") (pinfunction "1_1") (pintype "passive"))
      (node (ref "U8") (pin "31") (pinfunction "SNS10K/SYNC_31") (pintype "bidirectional"))
    )
    (net (code "133") (name "Net-(U8-SNS10{slash}DETECT16)") (class "Default")
      (node (ref "C55") (pin "1") (pinfunction "1_1") (pintype "passive"))
      (node (ref "U8") (pin "30") (pinfunction "SNS10/DETECT16_30") (pintype "bidirectional"))
    )
    (net (code "134") (name "Net-(U8-~{RESET})") (class "Default")
      (node (ref "R36") (pin "1") (pinfunction "1_1") (pintype "passive"))
      (node (ref "U8") (pin "29") (pinfunction "~{RESET}_29") (pintype "bidirectional"))
    )
    (net (code "135") (name "OUT_L") (class "Default")
      (node (ref "C36") (pin "2") (pinfunction "2_2") (pintype "passive"))
      (node (ref "PHONE_OUT") (pin "4") (pinfunction "L_4") (pintype "bidirectional"))
      (node (ref "R25") (pin "2") (pinfunction "2_2") (pintype "passive"))
    )
    (net (code "136") (name "OUT_R") (class "Default")
      (node (ref "C39") (pin "2") (pinfunction "2_2") (pintype "passive"))
      (node (ref "PHONE_OUT") (pin "1") (pinfunction "R_1") (pintype "bidirectional"))
    )
    (net (code "137") (name "PA_EN") (class "Default")
      (node (ref "L12") (pin "2") (pinfunction "2_2") (pintype "passive"))
      (node (ref "R10") (pin "2") (pinfunction "2_2") (pintype "passive"))
      (node (ref "U2") (pin "5") (pinfunction "PAEN_5") (pintype "bidirectional"))
    )
    (net (code "138") (name "PHONE_L") (class "Default")
      (node (ref "R28") (pin "1") (pinfunction "1_1") (pintype "passive"))
      (node (ref "U3") (pin "25") (pinfunction "HPL_25") (pintype "bidirectional"))
    )
    (net (code "139") (name "PHONE_R") (class "Default")
      (node (ref "R30") (pin "1") (pinfunction "1_1") (pintype "passive"))
      (node (ref "U3") (pin "27") (pinfunction "HPR_27") (pintype "bidirectional"))
    )
    (net (code "140") (name "PHONE_SENSE") (class "Default")
      (node (ref "PHONE_OUT") (pin "3") (pinfunction "L_SW_3") (pintype "bidirectional"))
      (node (ref "R24") (pin "1") (pinfunction "1_1") (pintype "passive"))
    )
    (net (code "141") (name "PROG_PWR") (class "Default")
      (node (ref "D1") (pin "2") (pinfunction "A_2") (pintype "passive"))
      (node (ref "ICSP") (pin "2") (pinfunction "2_2") (pintype "bidirectional"))
      (node (ref "SERIAL") (pin "3") (pinfunction "3_3") (pintype "bidirectional"))
    )
    (net (code "142") (name "RED") (class "Default")
      (node (ref "TO_AUX") (pin "4") (pinfunction "4_4") (pintype "bidirectional"))
    )
    (net (code "143") (name "RESET_AVR") (class "Default")
      (node (ref "C30") (pin "2") (pinfunction "2_2") (pintype "passive"))
      (node (ref "ICSP") (pin "5") (pinfunction "5_5") (pintype "bidirectional"))
      (node (ref "R11") (pin "1") (pinfunction "1_1") (pintype "passive"))
      (node (ref "U4") (pin "29") (pinfunction "PC6(~{RESET})_29") (pintype "bidirectional"))
    )
    (net (code "144") (name "RESET_CC8531") (class "Default")
      (node (ref "CCD") (pin "7") (pinfunction "7_7") (pintype "bidirectional"))
      (node (ref "L4") (pin "2") (pinfunction "2_2") (pintype "passive"))
      (node (ref "U4") (pin "26") (pinfunction "PC3(ADC3)_26") (pintype "bidirectional"))
    )
    (net (code "145") (name "RESET_CODEC") (class "Default")
      (node (ref "U3") (pin "31") (pinfunction "~{RESET}_31") (pintype "bidirectional"))
      (node (ref "U4") (pin "13") (pinfunction "PB1_13") (pintype "bidirectional"))
    )
    (net (code "146") (name "RF_N") (class "Default")
      (node (ref "U1") (pin "25") (pinfunction "RF_N_25") (pintype "bidirectional"))
      (node (ref "U2") (pin "2") (pinfunction "RF_N_2") (pintype "bidirectional"))
    )
    (net (code "147") (name "RF_P") (class "Default")
      (node (ref "U1") (pin "24") (pinfunction "RF_P_24") (pintype "bidirectional"))
      (node (ref "U2") (pin "4") (pinfunction "RF_P_4") (pintype "bidirectional"))
    )
    (net (code "148") (name "RX") (class "Default")
      (node (ref "SERIAL") (pin "4") (pinfunction "4_4") (pintype "bidirectional"))
      (node (ref "U4") (pin "31") (pinfunction "PD1(TXD)_31") (pintype "bidirectional"))
    )
    (net (code "149") (name "SCLK") (class "Default")
      (node (ref "CCD") (pin "6") (pinfunction "6_6") (pintype "bidirectional"))
      (node (ref "ICSP") (pin "3") (pinfunction "3_3") (pintype "bidirectional"))
      (node (ref "TO_AUX") (pin "1") (pinfunction "1_1") (pintype "bidirectional"))
      (node (ref "U1") (pin "4") (pinfunction "SCLK_4") (pintype "bidirectional"))
      (node (ref "U3") (pin "8") (pinfunction "SCLK/MFP3_8") (pintype "bidirectional"))
      (node (ref "U4") (pin "17") (pinfunction "PB5(SCK)_17") (pintype "bidirectional"))
      (node (ref "U7") (pin "110") (pinfunction "PA27_110") (pintype "bidirectional"))
    )
    (net (code "150") (name "SCLK_SD") (class "Default")
      (node (ref "MICROSD") (pin "CLK") (pinfunction "SCLK_CLK") (pintype "bidirectional"))
      (node (ref "U4") (pin "10") (pinfunction "PD6(AIN0)_10") (pintype "bidirectional"))
      (node (ref "U7") (pin "91") (pinfunction "PB20_91") (pintype "bidirectional"))
    )
    (net (code "151") (name "TX") (class "Default")
      (node (ref "SERIAL") (pin "5") (pinfunction "5_5") (pintype "bidirectional"))
      (node (ref "U4") (pin "30") (pinfunction "PD0(RXD)_30") (pintype "bidirectional"))
    )
    (net (code "152") (name "WCLK") (class "Default")
      (node (ref "L9") (pin "1") (pinfunction "1_1") (pintype "passive"))
      (node (ref "U3") (pin "3") (pinfunction "WCLK_3") (pintype "bidirectional"))
    )
    (net (code "153") (name "unconnected-(C37-Pad1)") (class "Default")
      (node (ref "C37") (pin "1") (pinfunction "1_1") (pintype "passive"))
    )
    (net (code "154") (name "unconnected-(C38-Pad1)") (class "Default")
      (node (ref "C38") (pin "1") (pinfunction "1_1") (pintype "passive"))
    )
    (net (code "155") (name "unconnected-(CCD-Pad3)") (class "Default")
      (node (ref "CCD") (pin "3") (pinfunction "3_3") (pintype "bidirectional"))
    )
    (net (code "156") (name "unconnected-(CCD-Pad4)") (class "Default")
      (node (ref "CCD") (pin "4") (pinfunction "4_4") (pintype "bidirectional"))
    )
    (net (code "157") (name "unconnected-(LINE_IN-R_SW-Pad2)") (class "Default")
      (node (ref "LINE_IN") (pin "2") (pinfunction "R_SW_2") (pintype "bidirectional"))
    )
    (net (code "158") (name "unconnected-(PHONE_OUT-R_SW-Pad2)") (class "Default")
      (node (ref "PHONE_OUT") (pin "2") (pinfunction "R_SW_2") (pintype "bidirectional"))
    )
    (net (code "159") (name "unconnected-(U1-GIO1-Pad7)") (class "Default")
      (node (ref "U1") (pin "7") (pinfunction "GIO1_7") (pintype "bidirectional"))
    )
    (net (code "160") (name "unconnected-(U1-SCL{slash}GIO10-Pad32)") (class "Default")
      (node (ref "U1") (pin "32") (pinfunction "SCL/GIO10_32") (pintype "bidirectional"))
    )
    (net (code "161") (name "unconnected-(U1-SDA{slash}GIO11-Pad33)") (class "Default")
      (node (ref "U1") (pin "33") (pinfunction "SDA/GIO11_33") (pintype "bidirectional"))
    )
    (net (code "162") (name "unconnected-(U2-RXTX-Pad3)") (class "Default")
      (node (ref "U2") (pin "3") (pinfunction "RXTX_3") (pintype "bidirectional"))
    )
    (net (code "163") (name "unconnected-(U3-GPIO{slash}MFP5-Pad32)") (class "Default")
      (node (ref "U3") (pin "32") (pinfunction "GPIO/MFP5_32") (pintype "bidirectional"))
    )
    (net (code "164") (name "unconnected-(U3-IN2_L-Pad15)") (class "Default")
      (node (ref "U3") (pin "15") (pinfunction "IN2_L_15") (pintype "bidirectional"))
    )
    (net (code "165") (name "unconnected-(U3-IN2_R-Pad16)") (class "Default")
      (node (ref "U3") (pin "16") (pinfunction "IN2_R_16") (pintype "bidirectional"))
    )
    (net (code "166") (name "unconnected-(U3-IN3_L-Pad20)") (class "Default")
      (node (ref "U3") (pin "20") (pinfunction "IN3_L_20") (pintype "bidirectional"))
    )
    (net (code "167") (name "unconnected-(U3-IN3_R-Pad21)") (class "Default")
      (node (ref "U3") (pin "21") (pinfunction "IN3_R_21") (pintype "bidirectional"))
    )
    (net (code "168") (name "unconnected-(U3-MICBIAS-Pad19)") (class "Default")
      (node (ref "U3") (pin "19") (pinfunction "MICBIAS_19") (pintype "bidirectional"))
    )
    (net (code "169") (name "unconnected-(U4-ADC6-Pad19)") (class "Default")
      (node (ref "U4") (pin "19") (pinfunction "ADC6_19") (pintype "bidirectional"))
    )
    (net (code "170") (name "unconnected-(U4-ADC7-Pad22)") (class "Default")
      (node (ref "U4") (pin "22") (pinfunction "ADC7_22") (pintype "bidirectional"))
    )
    (net (code "171") (name "unconnected-(U4-AREF-Pad20)") (class "Default")
      (node (ref "U4") (pin "20") (pinfunction "AREF_20") (pintype "bidirectional"))
    )
    (net (code "172") (name "unconnected-(U4-PB2(~{SS})-Pad14)") (class "Default")
      (node (ref "U4") (pin "14") (pinfunction "PB2(~{SS})_14") (pintype "bidirectional"))
    )
    (net (code "173") (name "unconnected-(U4-PC4(ADC4{slash}SDA)-Pad27)") (class "Default")
      (node (ref "U4") (pin "27") (pinfunction "PC4(ADC4/SDA)_27") (pintype "bidirectional"))
    )
    (net (code "174") (name "unconnected-(U4-PC5(ADC5{slash}SCL)-Pad28)") (class "Default")
      (node (ref "U4") (pin "28") (pinfunction "PC5(ADC5/SCL)_28") (pintype "bidirectional"))
    )
    (net (code "175") (name "unconnected-(U4-PD2-Pad32)") (class "Default")
      (node (ref "U4") (pin "32") (pinfunction "PD2_32") (pintype "bidirectional"))
    )
    (net (code "176") (name "unconnected-(U4-PD4(XCK)-Pad2)") (class "Default")
      (node (ref "U4") (pin "2") (pinfunction "PD4(XCK)_2") (pintype "bidirectional"))
    )
    (net (code "177") (name "unconnected-(U7A-PA0-Pad23)") (class "Default")
      (node (ref "U7") (pin "23") (pinfunction "PA0_23") (pintype "bidirectional"))
    )
    (net (code "178") (name "unconnected-(U7A-PA1-Pad24)") (class "Default")
      (node (ref "U7") (pin "24") (pinfunction "PA1_24") (pintype "bidirectional"))
    )
    (net (code "179") (name "unconnected-(U7A-PA2-Pad85)") (class "Default")
      (node (ref "U7") (pin "85") (pinfunction "PA2_85") (pintype "bidirectional"))
    )
    (net (code "180") (name "unconnected-(U7A-PA3-Pad84)") (class "Default")
      (node (ref "U7") (pin "84") (pinfunction "PA3_84") (pintype "bidirectional"))
    )
    (net (code "181") (name "unconnected-(U7A-PA4-Pad83)") (class "Default")
      (node (ref "U7") (pin "83") (pinfunction "PA4_83") (pintype "bidirectional"))
    )
    (net (code "182") (name "unconnected-(U7A-PA5-Pad25)") (class "Default")
      (node (ref "U7") (pin "25") (pinfunction "PA5_25") (pintype "bidirectional"))
    )
    (net (code "183") (name "unconnected-(U7A-PA6-Pad82)") (class "Default")
      (node (ref "U7") (pin "82") (pinfunction "PA6_82") (pintype "bidirectional"))
    )
    (net (code "184") (name "unconnected-(U7A-PA7-Pad26)") (class "Default")
      (node (ref "U7") (pin "26") (pinfunction "PA7_26") (pintype "bidirectional"))
    )
    (net (code "185") (name "unconnected-(U7A-PA8-Pad27)") (class "Default")
      (node (ref "U7") (pin "27") (pinfunction "PA8_27") (pintype "bidirectional"))
    )
    (net (code "186") (name "unconnected-(U7A-PA9-Pad2)") (class "Default")
      (node (ref "U7") (pin "2") (pinfunction "PA9_2") (pintype "bidirectional"))
    )
    (net (code "187") (name "unconnected-(U7A-PA10-Pad3)") (class "Default")
      (node (ref "U7") (pin "3") (pinfunction "PA10_3") (pintype "bidirectional"))
    )
    (net (code "188") (name "unconnected-(U7A-PA11-Pad4)") (class "Default")
      (node (ref "U7") (pin "4") (pinfunction "PA11_4") (pintype "bidirectional"))
    )
    (net (code "189") (name "unconnected-(U7A-PA12-Pad5)") (class "Default")
      (node (ref "U7") (pin "5") (pinfunction "PA12_5") (pintype "bidirectional"))
    )
    (net (code "190") (name "unconnected-(U7A-PA13-Pad6)") (class "Default")
      (node (ref "U7") (pin "6") (pinfunction "PA13_6") (pintype "bidirectional"))
    )
    (net (code "191") (name "unconnected-(U7A-PA14-Pad7)") (class "Default")
      (node (ref "U7") (pin "7") (pinfunction "PA14_7") (pintype "bidirectional"))
    )
    (net (code "192") (name "unconnected-(U7A-PA15-Pad8)") (class "Default")
      (node (ref "U7") (pin "8") (pinfunction "PA15_8") (pintype "bidirectional"))
    )
    (net (code "193") (name "unconnected-(U7A-PA16-Pad78)") (class "Default")
      (node (ref "U7") (pin "78") (pinfunction "PA16_78") (pintype "bidirectional"))
    )
    (net (code "194") (name "unconnected-(U7A-PA17-Pad9)") (class "Default")
      (node (ref "U7") (pin "9") (pinfunction "PA17_9") (pintype "bidirectional"))
    )
    (net (code "195") (name "unconnected-(U7A-PA18-Pad70)") (class "Default")
      (node (ref "U7") (pin "70") (pinfunction "PA18_70") (pintype "bidirectional"))
    )
    (net (code "196") (name "unconnected-(U7A-PA19-Pad71)") (class "Default")
      (node (ref "U7") (pin "71") (pinfunction "PA19_71") (pintype "bidirectional"))
    )
    (net (code "197") (name "unconnected-(U7A-PA20-Pad72)") (class "Default")
      (node (ref "U7") (pin "72") (pinfunction "PA20_72") (pintype "bidirectional"))
    )
    (net (code "198") (name "unconnected-(U7A-PA21-Pad107)") (class "Default")
      (node (ref "U7") (pin "107") (pinfunction "PA21_107") (pintype "bidirectional"))
    )
    (net (code "199") (name "unconnected-(U7A-PA22-Pad81)") (class "Default")
      (node (ref "U7") (pin "81") (pinfunction "PA22_81") (pintype "bidirectional"))
    )
    (net (code "200") (name "unconnected-(U7A-PA23-Pad80)") (class "Default")
      (node (ref "U7") (pin "80") (pinfunction "PA23_80") (pintype "bidirectional"))
    )
    (net (code "201") (name "unconnected-(U7A-PA24-Pad79)") (class "Default")
      (node (ref "U7") (pin "79") (pinfunction "PA24_79") (pintype "bidirectional"))
    )
    (net (code "202") (name "unconnected-(U7A-PA28-Pad111)") (class "Default")
      (node (ref "U7") (pin "111") (pinfunction "PA28_111") (pintype "bidirectional"))
    )
    (net (code "203") (name "unconnected-(U7A-PA29-Pad112)") (class "Default")
      (node (ref "U7") (pin "112") (pinfunction "PA29_112") (pintype "bidirectional"))
    )
    (net (code "204") (name "unconnected-(U7B-PB0-Pad113)") (class "Default")
      (node (ref "U7") (pin "113") (pinfunction "PB0_113") (pintype "bidirectional"))
    )
    (net (code "205") (name "unconnected-(U7B-PB1-Pad114)") (class "Default")
      (node (ref "U7") (pin "114") (pinfunction "PB1_114") (pintype "bidirectional"))
    )
    (net (code "206") (name "unconnected-(U7B-PB2-Pad115)") (class "Default")
      (node (ref "U7") (pin "115") (pinfunction "PB2_115") (pintype "bidirectional"))
    )
    (net (code "207") (name "unconnected-(U7B-PB3-Pad118)") (class "Default")
      (node (ref "U7") (pin "118") (pinfunction "PB3_118") (pintype "bidirectional"))
    )
    (net (code "208") (name "unconnected-(U7B-PB4-Pad119)") (class "Default")
      (node (ref "U7") (pin "119") (pinfunction "PB4_119") (pintype "bidirectional"))
    )
    (net (code "209") (name "unconnected-(U7B-PB5-Pad120)") (class "Default")
      (node (ref "U7") (pin "120") (pinfunction "PB5_120") (pintype "bidirectional"))
    )
    (net (code "210") (name "unconnected-(U7B-PB6-Pad121)") (class "Default")
      (node (ref "U7") (pin "121") (pinfunction "PB6_121") (pintype "bidirectional"))
    )
    (net (code "211") (name "unconnected-(U7B-PB7-Pad122)") (class "Default")
      (node (ref "U7") (pin "122") (pinfunction "PB7_122") (pintype "bidirectional"))
    )
    (net (code "212") (name "unconnected-(U7B-PB8-Pad123)") (class "Default")
      (node (ref "U7") (pin "123") (pinfunction "PB8_123") (pintype "bidirectional"))
    )
    (net (code "213") (name "unconnected-(U7B-PB9-Pad127)") (class "Default")
      (node (ref "U7") (pin "127") (pinfunction "PB9_127") (pintype "bidirectional"))
    )
    (net (code "214") (name "unconnected-(U7B-PB10-Pad128)") (class "Default")
      (node (ref "U7") (pin "128") (pinfunction "PB10_128") (pintype "bidirectional"))
    )
    (net (code "215") (name "unconnected-(U7B-PB11-Pad129)") (class "Default")
      (node (ref "U7") (pin "129") (pinfunction "PB11_129") (pintype "bidirectional"))
    )
    (net (code "216") (name "unconnected-(U7B-PB12-Pad86)") (class "Default")
      (node (ref "U7") (pin "86") (pinfunction "PB12_86") (pintype "bidirectional"))
    )
    (net (code "217") (name "unconnected-(U7B-PB13-Pad87)") (class "Default")
      (node (ref "U7") (pin "87") (pinfunction "PB13_87") (pintype "bidirectional"))
    )
    (net (code "218") (name "unconnected-(U7B-PB14-Pad140)") (class "Default")
      (node (ref "U7") (pin "140") (pinfunction "PB14_140") (pintype "bidirectional"))
    )
    (net (code "219") (name "unconnected-(U7B-PB15-Pad76)") (class "Default")
      (node (ref "U7") (pin "76") (pinfunction "PB15_76") (pintype "bidirectional"))
    )
    (net (code "220") (name "unconnected-(U7B-PB16-Pad77)") (class "Default")
      (node (ref "U7") (pin "77") (pinfunction "PB16_77") (pintype "bidirectional"))
    )
    (net (code "221") (name "unconnected-(U7B-PB22-Pad141)") (class "Default")
      (node (ref "U7") (pin "141") (pinfunction "PB22_141") (pintype "bidirectional"))
    )
    (net (code "222") (name "unconnected-(U7B-PB23-Pad142)") (class "Default")
      (node (ref "U7") (pin "142") (pinfunction "PB23_142") (pintype "bidirectional"))
    )
    (net (code "223") (name "unconnected-(U7B-PB24-Pad143)") (class "Default")
      (node (ref "U7") (pin "143") (pinfunction "PB24_143") (pintype "bidirectional"))
    )
    (net (code "224") (name "unconnected-(U7B-PB25-Pad144)") (class "Default")
      (node (ref "U7") (pin "144") (pinfunction "PB25_144") (pintype "bidirectional"))
    )
    (net (code "225") (name "unconnected-(U7B-PB26-Pad1)") (class "Default")
      (node (ref "U7") (pin "1") (pinfunction "PB26_1") (pintype "bidirectional"))
    )
    (net (code "226") (name "unconnected-(U7B-PB27-Pad68)") (class "Default")
      (node (ref "U7") (pin "68") (pinfunction "PB27_68") (pintype "bidirectional"))
    )
    (net (code "227") (name "unconnected-(U7B-PB28-Pad28)") (class "Default")
      (node (ref "U7") (pin "28") (pinfunction "PB28_28") (pintype "bidirectional"))
    )
    (net (code "228") (name "unconnected-(U7B-PB29-Pad29)") (class "Default")
      (node (ref "U7") (pin "29") (pinfunction "PB29_29") (pintype "bidirectional"))
    )
    (net (code "229") (name "unconnected-(U7B-PB30-Pad30)") (class "Default")
      (node (ref "U7") (pin "30") (pinfunction "PB30_30") (pintype "bidirectional"))
    )
    (net (code "230") (name "unconnected-(U7B-PB31-Pad31)") (class "Default")
      (node (ref "U7") (pin "31") (pinfunction "PB31_31") (pintype "bidirectional"))
    )
    (net (code "231") (name "unconnected-(U7C-PC0-Pad130)") (class "Default")
      (node (ref "U7") (pin "130") (pinfunction "PC0_130") (pintype "bidirectional"))
    )
    (net (code "232") (name "unconnected-(U7C-PC1-Pad55)") (class "Default")
      (node (ref "U7") (pin "55") (pinfunction "PC1_55") (pintype "bidirectional"))
    )
    (net (code "233") (name "unconnected-(U7C-PC2-Pad59)") (class "Default")
      (node (ref "U7") (pin "59") (pinfunction "PC2_59") (pintype "bidirectional"))
    )
    (net (code "234") (name "unconnected-(U7C-PC3-Pad60)") (class "Default")
      (node (ref "U7") (pin "60") (pinfunction "PC3_60") (pintype "bidirectional"))
    )
    (net (code "235") (name "unconnected-(U7C-PC4-Pad116)") (class "Default")
      (node (ref "U7") (pin "116") (pinfunction "PC4_116") (pintype "bidirectional"))
    )
    (net (code "236") (name "unconnected-(U7C-PC5-Pad63)") (class "Default")
      (node (ref "U7") (pin "63") (pinfunction "PC5_63") (pintype "bidirectional"))
    )
    (net (code "237") (name "unconnected-(U7C-PC6-Pad64)") (class "Default")
      (node (ref "U7") (pin "64") (pinfunction "PC6_64") (pintype "bidirectional"))
    )
    (net (code "238") (name "unconnected-(U7C-PC7-Pad65)") (class "Default")
      (node (ref "U7") (pin "65") (pinfunction "PC7_65") (pintype "bidirectional"))
    )
    (net (code "239") (name "unconnected-(U7C-PC8-Pad66)") (class "Default")
      (node (ref "U7") (pin "66") (pinfunction "PC8_66") (pintype "bidirectional"))
    )
    (net (code "240") (name "unconnected-(U7C-PC9-Pad67)") (class "Default")
      (node (ref "U7") (pin "67") (pinfunction "PC9_67") (pintype "bidirectional"))
    )
    (net (code "241") (name "unconnected-(U7C-PC10-Pad117)") (class "Default")
      (node (ref "U7") (pin "117") (pinfunction "PC10_117") (pintype "bidirectional"))
    )
    (net (code "242") (name "unconnected-(U7C-PC11-Pad93)") (class "Default")
      (node (ref "U7") (pin "93") (pinfunction "PC11_93") (pintype "bidirectional"))
    )
    (net (code "243") (name "unconnected-(U7C-PC12-Pad94)") (class "Default")
      (node (ref "U7") (pin "94") (pinfunction "PC12_94") (pintype "bidirectional"))
    )
    (net (code "244") (name "unconnected-(U7C-PC13-Pad95)") (class "Default")
      (node (ref "U7") (pin "95") (pinfunction "PC13_95") (pintype "bidirectional"))
    )
    (net (code "245") (name "unconnected-(U7C-PC14-Pad96)") (class "Default")
      (node (ref "U7") (pin "96") (pinfunction "PC14_96") (pintype "bidirectional"))
    )
    (net (code "246") (name "unconnected-(U7C-PC15-Pad97)") (class "Default")
      (node (ref "U7") (pin "97") (pinfunction "PC15_97") (pintype "bidirectional"))
    )
    (net (code "247") (name "unconnected-(U7C-PC16-Pad98)") (class "Default")
      (node (ref "U7") (pin "98") (pinfunction "PC16_98") (pintype "bidirectional"))
    )
    (net (code "248") (name "unconnected-(U7C-PC17-Pad99)") (class "Default")
      (node (ref "U7") (pin "99") (pinfunction "PC17_99") (pintype "bidirectional"))
    )
    (net (code "249") (name "unconnected-(U7C-PC18-Pad100)") (class "Default")
      (node (ref "U7") (pin "100") (pinfunction "PC18_100") (pintype "bidirectional"))
    )
    (net (code "250") (name "unconnected-(U7C-PC19-Pad101)") (class "Default")
      (node (ref "U7") (pin "101") (pinfunction "PC19_101") (pintype "bidirectional"))
    )
    (net (code "251") (name "unconnected-(U7C-PC20-Pad131)") (class "Default")
      (node (ref "U7") (pin "131") (pinfunction "PC20_131") (pintype "bidirectional"))
    )
    (net (code "252") (name "unconnected-(U7C-PC21-Pad132)") (class "Default")
      (node (ref "U7") (pin "132") (pinfunction "PC21_132") (pintype "bidirectional"))
    )
    (net (code "253") (name "unconnected-(U7C-PC22-Pad133)") (class "Default")
      (node (ref "U7") (pin "133") (pinfunction "PC22_133") (pintype "bidirectional"))
    )
    (net (code "254") (name "unconnected-(U7C-PC23-Pad134)") (class "Default")
      (node (ref "U7") (pin "134") (pinfunction "PC23_134") (pintype "bidirectional"))
    )
    (net (code "255") (name "unconnected-(U7C-PC24-Pad135)") (class "Default")
      (node (ref "U7") (pin "135") (pinfunction "PC24_135") (pintype "bidirectional"))
    )
    (net (code "256") (name "unconnected-(U7C-PC25-Pad136)") (class "Default")
      (node (ref "U7") (pin "136") (pinfunction "PC25_136") (pintype "bidirectional"))
    )
    (net (code "257") (name "unconnected-(U7C-PC26-Pad137)") (class "Default")
      (node (ref "U7") (pin "137") (pinfunction "PC26_137") (pintype "bidirectional"))
    )
    (net (code "258") (name "unconnected-(U7C-PC27-Pad138)") (class "Default")
      (node (ref "U7") (pin "138") (pinfunction "PC27_138") (pintype "bidirectional"))
    )
    (net (code "259") (name "unconnected-(U7C-PC28-Pad139)") (class "Default")
      (node (ref "U7") (pin "139") (pinfunction "PC28_139") (pintype "bidirectional"))
    )
    (net (code "260") (name "unconnected-(U7C-PC29-Pad102)") (class "Default")
      (node (ref "U7") (pin "102") (pinfunction "PC29_102") (pintype "bidirectional"))
    )
    (net (code "261") (name "unconnected-(U7C-PC30-Pad103)") (class "Default")
      (node (ref "U7") (pin "103") (pinfunction "PC30_103") (pintype "bidirectional"))
    )
    (net (code "262") (name "unconnected-(U7D-PD0-Pad13)") (class "Default")
      (node (ref "U7") (pin "13") (pinfunction "PD0_13") (pintype "bidirectional"))
    )
    (net (code "263") (name "unconnected-(U7D-PD1-Pad14)") (class "Default")
      (node (ref "U7") (pin "14") (pinfunction "PD1_14") (pintype "bidirectional"))
    )
    (net (code "264") (name "unconnected-(U7D-PD2-Pad15)") (class "Default")
      (node (ref "U7") (pin "15") (pinfunction "PD2_15") (pintype "bidirectional"))
    )
    (net (code "265") (name "unconnected-(U7D-PD3-Pad16)") (class "Default")
      (node (ref "U7") (pin "16") (pinfunction "PD3_16") (pintype "bidirectional"))
    )
    (net (code "266") (name "unconnected-(U7D-PD4-Pad17)") (class "Default")
      (node (ref "U7") (pin "17") (pinfunction "PD4_17") (pintype "bidirectional"))
    )
    (net (code "267") (name "unconnected-(U7D-PD5-Pad18)") (class "Default")
      (node (ref "U7") (pin "18") (pinfunction "PD5_18") (pintype "bidirectional"))
    )
    (net (code "268") (name "unconnected-(U7D-PD6-Pad19)") (class "Default")
      (node (ref "U7") (pin "19") (pinfunction "PD6_19") (pintype "bidirectional"))
    )
    (net (code "269") (name "unconnected-(U7D-PD7-Pad20)") (class "Default")
      (node (ref "U7") (pin "20") (pinfunction "PD7_20") (pintype "bidirectional"))
    )
    (net (code "270") (name "unconnected-(U7D-PD8-Pad21)") (class "Default")
      (node (ref "U7") (pin "21") (pinfunction "PD8_21") (pintype "bidirectional"))
    )
    (net (code "271") (name "unconnected-(U7D-PD9-Pad22)") (class "Default")
      (node (ref "U7") (pin "22") (pinfunction "PD9_22") (pintype "bidirectional"))
    )
    (net (code "272") (name "unconnected-(U7D-PD10-Pad32)") (class "Default")
      (node (ref "U7") (pin "32") (pinfunction "PD10_32") (pintype "bidirectional"))
    )
    (net (code "273") (name "unconnected-(U7E-GNDANA-Pad74)") (class "Default")
      (node (ref "U7") (pin "74") (pinfunction "GNDANA_74") (pintype "bidirectional"))
    )
    (net (code "274") (name "unconnected-(U7E-GNDBU-Pad54)") (class "Default")
      (node (ref "U7") (pin "54") (pinfunction "GNDBU_54") (pintype "bidirectional"))
    )
    (net (code "275") (name "unconnected-(U7E-GNDPLL-Pad33)") (class "Default")
      (node (ref "U7") (pin "33") (pinfunction "GNDPLL_33") (pintype "bidirectional"))
    )
    (net (code "276") (name "unconnected-(U7E-GNDUTMI-Pad44)") (class "Default")
      (node (ref "U7") (pin "44") (pinfunction "GNDUTMI_44") (pintype "bidirectional"))
    )
    (net (code "277") (name "unconnected-(U7E-GND_1-Pad12)") (class "Default")
      (node (ref "U7") (pin "12") (pinfunction "GND_1_12") (pintype "bidirectional"))
    )
    (net (code "278") (name "unconnected-(U7E-GND_2-Pad58)") (class "Default")
      (node (ref "U7") (pin "58") (pinfunction "GND_2_58") (pintype "bidirectional"))
    )
    (net (code "279") (name "unconnected-(U7E-GND_3-Pad106)") (class "Default")
      (node (ref "U7") (pin "106") (pinfunction "GND_3_106") (pintype "bidirectional"))
    )
    (net (code "280") (name "unconnected-(U7E-GND_4-Pad126)") (class "Default")
      (node (ref "U7") (pin "126") (pinfunction "GND_4_126") (pintype "bidirectional"))
    )
    (net (code "281") (name "unconnected-(U7E-VDDANA-Pad73)") (class "Default")
      (node (ref "U7") (pin "73") (pinfunction "VDDANA_73") (pintype "bidirectional"))
    )
    (net (code "282") (name "unconnected-(U7F-ADVREF-Pad75)") (class "Default")
      (node (ref "U7") (pin "75") (pinfunction "ADVREF_75") (pintype "bidirectional"))
    )
    (net (code "283") (name "unconnected-(U7F-DFSDM-Pad43)") (class "Default")
      (node (ref "U7") (pin "43") (pinfunction "DFSDM_43") (pintype "bidirectional"))
    )
    (net (code "284") (name "unconnected-(U7F-DFSDP-Pad42)") (class "Default")
      (node (ref "U7") (pin "42") (pinfunction "DFSDP_42") (pintype "bidirectional"))
    )
    (net (code "285") (name "unconnected-(U7F-DHSDM-Pad38)") (class "Default")
      (node (ref "U7") (pin "38") (pinfunction "DHSDM_38") (pintype "bidirectional"))
    )
    (net (code "286") (name "unconnected-(U7F-DHSDP-Pad37)") (class "Default")
      (node (ref "U7") (pin "37") (pinfunction "DHSDP_37") (pintype "bidirectional"))
    )
    (net (code "287") (name "unconnected-(U7F-FWUP-Pad53)") (class "Default")
      (node (ref "U7") (pin "53") (pinfunction "FWUP_53") (pintype "bidirectional"))
    )
    (net (code "288") (name "unconnected-(U7F-JTAGSEL-Pad46)") (class "Default")
      (node (ref "U7") (pin "46") (pinfunction "JTAGSEL_46") (pintype "bidirectional"))
    )
    (net (code "289") (name "unconnected-(U7F-NRST-Pad69)") (class "Default")
      (node (ref "U7") (pin "69") (pinfunction "NRST_69") (pintype "bidirectional"))
    )
    (net (code "290") (name "unconnected-(U7F-NRSTB-Pad47)") (class "Default")
      (node (ref "U7") (pin "47") (pinfunction "NRSTB_47") (pintype "bidirectional"))
    )
    (net (code "291") (name "unconnected-(U7F-SHDN-Pad50)") (class "Default")
      (node (ref "U7") (pin "50") (pinfunction "SHDN_50") (pintype "bidirectional"))
    )
    (net (code "292") (name "unconnected-(U7F-TST-Pad51)") (class "Default")
      (node (ref "U7") (pin "51") (pinfunction "TST_51") (pintype "bidirectional"))
    )
    (net (code "293") (name "unconnected-(U7F-VBG-Pad40)") (class "Default")
      (node (ref "U7") (pin "40") (pinfunction "VBG_40") (pintype "bidirectional"))
    )
    (net (code "294") (name "unconnected-(U7F-VBUS-Pad39)") (class "Default")
      (node (ref "U7") (pin "39") (pinfunction "VBUS_39") (pintype "bidirectional"))
    )
    (net (code "295") (name "unconnected-(U7F-XIN32-Pad48)") (class "Default")
      (node (ref "U7") (pin "48") (pinfunction "XIN32_48") (pintype "bidirectional"))
    )
    (net (code "296") (name "unconnected-(U7F-XOUT32-Pad49)") (class "Default")
      (node (ref "U7") (pin "49") (pinfunction "XOUT32_49") (pintype "bidirectional"))
    )
    (net (code "297") (name "unconnected-(U8-SNS0-Pad32)") (class "Default")
      (node (ref "U8") (pin "32") (pinfunction "SNS0_32") (pintype "bidirectional"))
    )
    (net (code "298") (name "unconnected-(U8-SNS0K-Pad1)") (class "Default")
      (node (ref "U8") (pin "1") (pinfunction "SNS0K_1") (pintype "bidirectional"))
    )
    (net (code "299") (name "unconnected-(U8-SNS1-Pad2)") (class "Default")
      (node (ref "U8") (pin "2") (pinfunction "SNS1_2") (pintype "bidirectional"))
    )
    (net (code "300") (name "unconnected-(U8-SNS1K-Pad3)") (class "Default")
      (node (ref "U8") (pin "3") (pinfunction "SNS1K_3") (pintype "bidirectional"))
    )
    (net (code "301") (name "unconnected-(U8-SNS2-Pad7)") (class "Default")
      (node (ref "U8") (pin "7") (pinfunction "SNS2_7") (pintype "bidirectional"))
    )
    (net (code "302") (name "unconnected-(U8-SNS2K-Pad6)") (class "Default")
      (node (ref "U8") (pin "6") (pinfunction "SNS2K_6") (pintype "bidirectional"))
    )
    (net (code "303") (name "unconnected-(USB-ID-Pad4)") (class "Default")
      (node (ref "USB") (pin "4") (pinfunction "ID_4") (pintype "bidirectional"))
    )
  )
)
